# Mega_2560_Z21.net
KiCad netlist of a schematic drawn in EAGLE
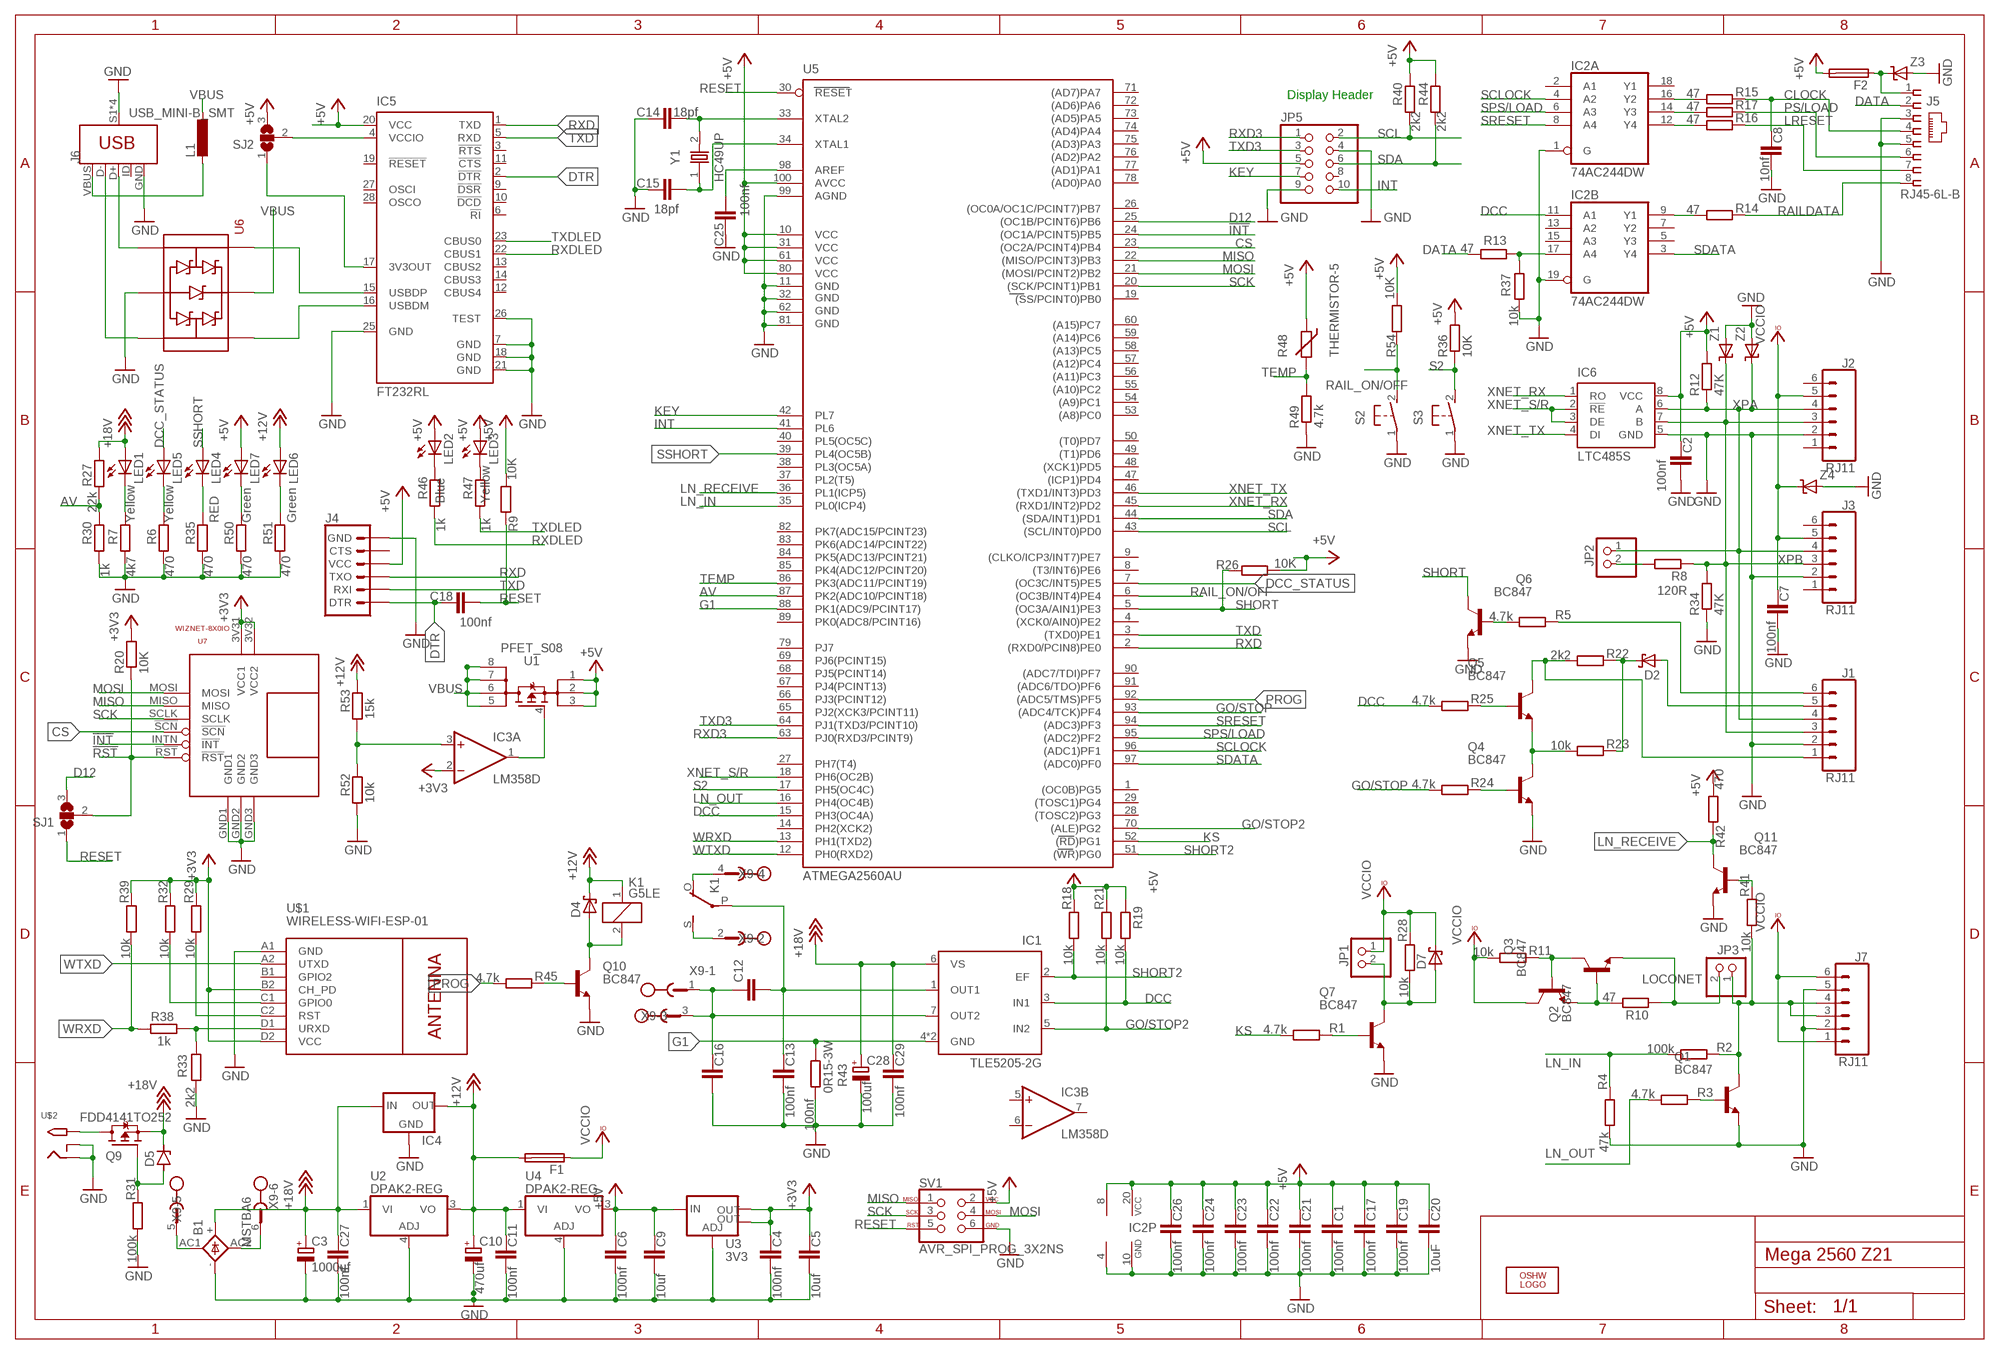
[diagram p0: schematic, sheet 1]

(export (version "E")
  (design (tool "Eeschema 10.0.6"))
  (components
    (comp (ref "B1")
      (value "BRIDGE_RECTIFIER_6AMP")
      (footprint "eagle-import:KBU-6D")
      (fields (field (name "PARTNUMBER") "KBU 6D"))
      (libsource (lib "eagle-import") (part "BRIDGE_RECTIFIER_6AMP"))
    )
    (comp (ref "C1")
      (value "100nf")
      (footprint "eagle-import:C0603")
      (libsource (lib "eagle-import") (part "C-EUC0603"))
    )
    (comp (ref "C2")
      (value "100nf")
      (footprint "eagle-import:C0603")
      (libsource (lib "eagle-import") (part "C-EUC0603"))
    )
    (comp (ref "C3")
      (value "1000uf")
      (footprint "eagle-import:E5-13")
      (libsource (lib "eagle-import") (part "rcl_334_CPOL-EUE5-13"))
    )
    (comp (ref "C4")
      (value "100nf")
      (footprint "eagle-import:C0603")
      (libsource (lib "eagle-import") (part "C-EUC0603"))
    )
    (comp (ref "C5")
      (value "10uf")
      (footprint "eagle-import:C0805")
      (libsource (lib "eagle-import") (part "C-EUC0805"))
    )
    (comp (ref "C6")
      (value "100nf")
      (footprint "eagle-import:C0603")
      (libsource (lib "eagle-import") (part "C-EUC0603"))
    )
    (comp (ref "C7")
      (value "100nf")
      (footprint "eagle-import:C0603")
      (libsource (lib "eagle-import") (part "C-EUC0603"))
    )
    (comp (ref "C8")
      (value "10nf")
      (footprint "eagle-import:C0603")
      (libsource (lib "eagle-import") (part "C-EUC0603"))
    )
    (comp (ref "C9")
      (value "10uf")
      (footprint "eagle-import:C0805")
      (libsource (lib "eagle-import") (part "C-EUC0805"))
    )
    (comp (ref "C10")
      (value "470uf")
      (footprint "eagle-import:E5-13")
      (libsource (lib "eagle-import") (part "rcl_334_CPOL-EUE5-13"))
    )
    (comp (ref "C11")
      (value "100nf")
      (footprint "eagle-import:C0603")
      (libsource (lib "eagle-import") (part "C-EUC0603"))
    )
    (comp (ref "C12")
      (value "C-EUC1812")
      (footprint "eagle-import:C1812")
      (libsource (lib "eagle-import") (part "C-EUC1812"))
    )
    (comp (ref "C13")
      (value "100nf")
      (footprint "eagle-import:C1206")
      (libsource (lib "eagle-import") (part "C-EUC1206"))
    )
    (comp (ref "C14")
      (value "18pf")
      (footprint "eagle-import:C0603")
      (libsource (lib "eagle-import") (part "C-EUC0603"))
    )
    (comp (ref "C15")
      (value "18pf")
      (footprint "eagle-import:C0603")
      (libsource (lib "eagle-import") (part "C-EUC0603"))
    )
    (comp (ref "C16")
      (value "100nf")
      (footprint "eagle-import:C1206")
      (libsource (lib "eagle-import") (part "C-EUC1206"))
    )
    (comp (ref "C17")
      (value "100nf")
      (footprint "eagle-import:C0603")
      (libsource (lib "eagle-import") (part "C-EUC0603"))
    )
    (comp (ref "C18")
      (value "100nf")
      (footprint "eagle-import:C0603")
      (libsource (lib "eagle-import") (part "C-EUC0603"))
    )
    (comp (ref "C19")
      (value "100nf")
      (footprint "eagle-import:C0603")
      (libsource (lib "eagle-import") (part "C-EUC0603"))
    )
    (comp (ref "C20")
      (value "10uF")
      (footprint "eagle-import:C0805")
      (libsource (lib "eagle-import") (part "C-EUC0805"))
    )
    (comp (ref "C21")
      (value "100nf")
      (footprint "eagle-import:C0603")
      (libsource (lib "eagle-import") (part "C-EUC0603"))
    )
    (comp (ref "C22")
      (value "100nf")
      (footprint "eagle-import:C0603")
      (libsource (lib "eagle-import") (part "C-EUC0603"))
    )
    (comp (ref "C23")
      (value "100nf")
      (footprint "eagle-import:C0603")
      (libsource (lib "eagle-import") (part "C-EUC0603"))
    )
    (comp (ref "C24")
      (value "100nf")
      (footprint "eagle-import:C0603")
      (libsource (lib "eagle-import") (part "C-EUC0603"))
    )
    (comp (ref "C25")
      (value "100nf")
      (footprint "eagle-import:C0603")
      (libsource (lib "eagle-import") (part "C-EUC0603"))
    )
    (comp (ref "C26")
      (value "100nf")
      (footprint "eagle-import:C0603")
      (libsource (lib "eagle-import") (part "C-EUC0603"))
    )
    (comp (ref "C27")
      (value "100nf")
      (footprint "eagle-import:C0805")
      (libsource (lib "eagle-import") (part "C-EUC0805"))
    )
    (comp (ref "C28")
      (value "100uf")
      (footprint "eagle-import:E2-5")
      (libsource (lib "eagle-import") (part "CPOL-EUE2-5"))
    )
    (comp (ref "C29")
      (value "100nf")
      (footprint "eagle-import:C1206")
      (libsource (lib "eagle-import") (part "C-EUC1206"))
    )
    (comp (ref "D2")
      (value "MICROSMD-SCHOTTKY-DIODE")
      (footprint "eagle-import:MICROSMP")
      (fields (field (name "MANUFACTURER") "Vishay"))
      (libsource (lib "eagle-import") (part "MICROSMD-SCHOTTKY-DIODE"))
    )
    (comp (ref "D4")
      (value "MICROSMD-SCHOTTKY-DIODE")
      (footprint "eagle-import:MICROSMP")
      (fields (field (name "MANUFACTURER") "Vishay"))
      (libsource (lib "eagle-import") (part "MICROSMD-SCHOTTKY-DIODE"))
    )
    (comp (ref "D5")
      (value "ZENER-DIODESOT23")
      (footprint "eagle-import:SOT23")
      (libsource (lib "eagle-import") (part "ZENER-DIODESOT23"))
    )
    (comp (ref "D7")
      (value "MICROSMD-SCHOTTKY-DIODE")
      (footprint "eagle-import:MICROSMP")
      (fields (field (name "MANUFACTURER") "Vishay"))
      (libsource (lib "eagle-import") (part "MICROSMD-SCHOTTKY-DIODE"))
    )
    (comp (ref "F1")
      (value "TE5")
      (footprint "eagle-import:TE5")
      (libsource (lib "eagle-import") (part "TE5"))
    )
    (comp (ref "F2")
      (value "TE5")
      (footprint "eagle-import:TE5")
      (libsource (lib "eagle-import") (part "TE5"))
    )
    (comp (ref "IC1")
      (value "TLE5205-2G")
      (footprint "eagle-import:P-TO263-7-1")
      (libsource (lib "eagle-import") (part "TLE5205-2G"))
    )
    (comp (ref "IC2")
      (value "74AC244DW")
      (footprint "eagle-import:SO20W")
      (libsource (lib "eagle-import") (part "74244DWAC"))
    )
    (comp (ref "IC3")
      (value "LM358D")
      (footprint "eagle-import:SO08")
      (libsource (lib "eagle-import") (part "LM358D"))
    )
    (comp (ref "IC4")
      (value "78XXS")
      (footprint "eagle-import:78XXS")
      (libsource (lib "eagle-import") (part "78XXS"))
    )
    (comp (ref "IC5")
      (value "FT232RL")
      (footprint "eagle-import:SSOP28")
      (libsource (lib "eagle-import") (part "FT232RL"))
    )
    (comp (ref "IC6")
      (value "LTC485S")
      (footprint "eagle-import:SOIC8")
      (libsource (lib "eagle-import") (part "LTC485S"))
    )
    (comp (ref "J1")
      (value "RJ11")
      (footprint "eagle-import:RJ11-6")
      (libsource (lib "eagle-import") (part "RJ11-6"))
    )
    (comp (ref "J2")
      (value "RJ11")
      (footprint "eagle-import:RJ11-6")
      (libsource (lib "eagle-import") (part "RJ11-6"))
    )
    (comp (ref "J3")
      (value "RJ11")
      (footprint "eagle-import:RJ11-6")
      (libsource (lib "eagle-import") (part "RJ11-6"))
    )
    (comp (ref "J4")
      (value "6_PIN_SERIAL_TARGET")
      (footprint "eagle-import:1X06")
      (libsource (lib "eagle-import") (part "6_PIN_SERIAL_TARGET"))
    )
    (comp (ref "J5")
      (value "RJ45-6L-B")
      (footprint "eagle-import:RJ45-NO-SHIELD")
      (libsource (lib "eagle-import") (part "RJ45-6L-B"))
    )
    (comp (ref "J6")
      (value "USB_MINI-B_SMT")
      (footprint "eagle-import:USB-MINIB")
      (libsource (lib "eagle-import") (part "USB_MINI-B_SMT"))
    )
    (comp (ref "J7")
      (value "RJ11")
      (footprint "eagle-import:RJ11-6")
      (libsource (lib "eagle-import") (part "RJ11-6"))
    )
    (comp (ref "JP1")
      (value "PINHD-1X2")
      (footprint "eagle-import:1X02")
      (libsource (lib "eagle-import") (part "PINHD-1X2"))
    )
    (comp (ref "JP2")
      (value "PINHD-1X2")
      (footprint "eagle-import:1X02")
      (libsource (lib "eagle-import") (part "PINHD-1X2"))
    )
    (comp (ref "JP3")
      (value "PINHD-1X2")
      (footprint "eagle-import:1X02")
      (libsource (lib "eagle-import") (part "PINHD-1X2"))
    )
    (comp (ref "JP5")
      (value "PINHD-2X5")
      (footprint "eagle-import:2X05")
      (libsource (lib "eagle-import") (part "PINHD-2X5"))
    )
    (comp (ref "K1")
      (value "G5LE")
      (footprint "eagle-import:G5LE")
      (libsource (lib "eagle-import") (part "G5LE"))
    )
    (comp (ref "L1")
      (value "L-EUL2012C")
      (footprint "eagle-import:L2012C")
      (libsource (lib "eagle-import") (part "L-EUL2012C"))
    )
    (comp (ref "LED1")
      (value "Yellow")
      (footprint "eagle-import:LED3MM")
      (libsource (lib "eagle-import") (part "LED3MM"))
    )
    (comp (ref "LED2")
      (value "Blue")
      (footprint "eagle-import:LED3MM")
      (libsource (lib "eagle-import") (part "LED3MM"))
    )
    (comp (ref "LED3")
      (value "Yellow")
      (footprint "eagle-import:LED3MM")
      (libsource (lib "eagle-import") (part "LED3MM"))
    )
    (comp (ref "LED4")
      (value "RED")
      (footprint "eagle-import:LED3MM")
      (libsource (lib "eagle-import") (part "LED3MM"))
    )
    (comp (ref "LED5")
      (value "Yellow")
      (footprint "eagle-import:LED3MM")
      (libsource (lib "eagle-import") (part "LED3MM"))
    )
    (comp (ref "LED6")
      (value "Green")
      (footprint "eagle-import:LED3MM")
      (libsource (lib "eagle-import") (part "LED3MM"))
    )
    (comp (ref "LED7")
      (value "Green")
      (footprint "eagle-import:LED3MM")
      (libsource (lib "eagle-import") (part "LED3MM"))
    )
    (comp (ref "LOGO1")
      (value "OSHW_LOGO_6MILX0200-NT")
      (footprint "eagle-import:OSHW_6X200_NOTEXT")
      (libsource (lib "eagle-import") (part "OSHW_LOGO_6MILX0200-NT"))
    )
    (comp (ref "Q1")
      (value "BC847")
      (footprint "eagle-import:SOT23")
      (libsource (lib "eagle-import") (part "BC847"))
    )
    (comp (ref "Q2")
      (value "BC847")
      (footprint "eagle-import:SOT23")
      (libsource (lib "eagle-import") (part "BC847"))
    )
    (comp (ref "Q3")
      (value "BC847")
      (footprint "eagle-import:SOT23")
      (libsource (lib "eagle-import") (part "BC847"))
    )
    (comp (ref "Q4")
      (value "BC847")
      (footprint "eagle-import:SOT23")
      (libsource (lib "eagle-import") (part "BC847"))
    )
    (comp (ref "Q5")
      (value "BC847")
      (footprint "eagle-import:SOT23")
      (libsource (lib "eagle-import") (part "BC847"))
    )
    (comp (ref "Q6")
      (value "BC847")
      (footprint "eagle-import:SOT23")
      (libsource (lib "eagle-import") (part "BC847"))
    )
    (comp (ref "Q7")
      (value "BC847")
      (footprint "eagle-import:SOT23")
      (libsource (lib "eagle-import") (part "BC847"))
    )
    (comp (ref "Q9")
      (value "FDD4141TO252")
      (footprint "eagle-import:TO252")
      (libsource (lib "eagle-import") (part "FDD4141TO252"))
    )
    (comp (ref "Q10")
      (value "BC847")
      (footprint "eagle-import:SOT23")
      (libsource (lib "eagle-import") (part "BC847"))
    )
    (comp (ref "Q11")
      (value "BC847")
      (footprint "eagle-import:SOT23")
      (libsource (lib "eagle-import") (part "BC847"))
    )
    (comp (ref "R1")
      (value "4.7k")
      (footprint "eagle-import:R0603")
      (libsource (lib "eagle-import") (part "R-EU_R0603"))
    )
    (comp (ref "R2")
      (value "100k")
      (footprint "eagle-import:R0603")
      (libsource (lib "eagle-import") (part "R-EU_R0603"))
    )
    (comp (ref "R3")
      (value "4.7k")
      (footprint "eagle-import:R0603")
      (libsource (lib "eagle-import") (part "R-EU_R0603"))
    )
    (comp (ref "R4")
      (value "47k")
      (footprint "eagle-import:R0603")
      (libsource (lib "eagle-import") (part "R-EU_R0603"))
    )
    (comp (ref "R5")
      (value "4.7k")
      (footprint "eagle-import:R0603")
      (libsource (lib "eagle-import") (part "R-EU_R0603"))
    )
    (comp (ref "R6")
      (value "470")
      (footprint "eagle-import:R0603")
      (libsource (lib "eagle-import") (part "R-EU_R0603"))
    )
    (comp (ref "R7")
      (value "4k7")
      (footprint "eagle-import:R0603")
      (libsource (lib "eagle-import") (part "R-EU_R0603"))
    )
    (comp (ref "R8")
      (value "120R")
      (footprint "eagle-import:R0603")
      (libsource (lib "eagle-import") (part "R-EU_R0603"))
    )
    (comp (ref "R9")
      (value "10K")
      (footprint "eagle-import:R0603")
      (libsource (lib "eagle-import") (part "R-EU_R0603"))
    )
    (comp (ref "R10")
      (value "47")
      (footprint "eagle-import:R0603")
      (libsource (lib "eagle-import") (part "R-EU_R0603"))
    )
    (comp (ref "R11")
      (value "10k")
      (footprint "eagle-import:R0603")
      (libsource (lib "eagle-import") (part "R-EU_R0603"))
    )
    (comp (ref "R12")
      (value "47K")
      (footprint "eagle-import:R0603")
      (libsource (lib "eagle-import") (part "R-EU_R0603"))
    )
    (comp (ref "R13")
      (value "47")
      (footprint "eagle-import:R0603")
      (libsource (lib "eagle-import") (part "R-EU_R0603"))
    )
    (comp (ref "R14")
      (value "47")
      (footprint "eagle-import:R0603")
      (libsource (lib "eagle-import") (part "R-EU_R0603"))
    )
    (comp (ref "R15")
      (value "47")
      (footprint "eagle-import:R0603")
      (libsource (lib "eagle-import") (part "R-EU_R0603"))
    )
    (comp (ref "R16")
      (value "47")
      (footprint "eagle-import:R0603")
      (libsource (lib "eagle-import") (part "R-EU_R0603"))
    )
    (comp (ref "R17")
      (value "47")
      (footprint "eagle-import:R0603")
      (libsource (lib "eagle-import") (part "R-EU_R0603"))
    )
    (comp (ref "R18")
      (value "10k")
      (footprint "eagle-import:R0603")
      (libsource (lib "eagle-import") (part "R-EU_R0603"))
    )
    (comp (ref "R19")
      (value "10k")
      (footprint "eagle-import:R0603")
      (libsource (lib "eagle-import") (part "R-EU_R0603"))
    )
    (comp (ref "R20")
      (value "10K")
      (footprint "eagle-import:R0603")
      (libsource (lib "eagle-import") (part "R-EU_R0603"))
    )
    (comp (ref "R21")
      (value "10k")
      (footprint "eagle-import:R0603")
      (libsource (lib "eagle-import") (part "R-EU_R0603"))
    )
    (comp (ref "R22")
      (value "2k2")
      (footprint "eagle-import:R0603")
      (libsource (lib "eagle-import") (part "R-EU_R0603"))
    )
    (comp (ref "R23")
      (value "10k")
      (footprint "eagle-import:R0603")
      (libsource (lib "eagle-import") (part "R-EU_R0603"))
    )
    (comp (ref "R24")
      (value "4.7k")
      (footprint "eagle-import:R0603")
      (libsource (lib "eagle-import") (part "R-EU_R0603"))
    )
    (comp (ref "R25")
      (value "4.7k")
      (footprint "eagle-import:R0603")
      (libsource (lib "eagle-import") (part "R-EU_R0603"))
    )
    (comp (ref "R26")
      (value "10K")
      (footprint "eagle-import:R0603")
      (libsource (lib "eagle-import") (part "R-EU_R0603"))
    )
    (comp (ref "R27")
      (value "22k")
      (footprint "eagle-import:R0603")
      (libsource (lib "eagle-import") (part "R-EU_R0603"))
    )
    (comp (ref "R28")
      (value "10k")
      (footprint "eagle-import:R0603")
      (libsource (lib "eagle-import") (part "R-EU_R0603"))
    )
    (comp (ref "R29")
      (value "10k")
      (footprint "eagle-import:R0603")
      (libsource (lib "eagle-import") (part "R-EU_R0603"))
    )
    (comp (ref "R30")
      (value "1k")
      (footprint "eagle-import:R0603")
      (libsource (lib "eagle-import") (part "R-EU_R0603"))
    )
    (comp (ref "R31")
      (value "100k")
      (footprint "eagle-import:R0603")
      (libsource (lib "eagle-import") (part "R-EU_R0603"))
    )
    (comp (ref "R32")
      (value "10k")
      (footprint "eagle-import:R0603")
      (libsource (lib "eagle-import") (part "R-EU_R0603"))
    )
    (comp (ref "R33")
      (value "2k2")
      (footprint "eagle-import:R0603")
      (libsource (lib "eagle-import") (part "R-EU_R0603"))
    )
    (comp (ref "R34")
      (value "47K")
      (footprint "eagle-import:R0603")
      (libsource (lib "eagle-import") (part "R-EU_R0603"))
    )
    (comp (ref "R35")
      (value "470")
      (footprint "eagle-import:R0603")
      (libsource (lib "eagle-import") (part "R-EU_R0603"))
    )
    (comp (ref "R36")
      (value "10K")
      (footprint "eagle-import:R0603")
      (libsource (lib "eagle-import") (part "R-EU_R0603"))
    )
    (comp (ref "R37")
      (value "10k")
      (footprint "eagle-import:R0603")
      (libsource (lib "eagle-import") (part "R-EU_R0603"))
    )
    (comp (ref "R38")
      (value "1k")
      (footprint "eagle-import:R0603")
      (libsource (lib "eagle-import") (part "R-EU_R0603"))
    )
    (comp (ref "R39")
      (value "10k")
      (footprint "eagle-import:R0603")
      (libsource (lib "eagle-import") (part "R-EU_R0603"))
    )
    (comp (ref "R40")
      (value "2k2")
      (footprint "eagle-import:R0603")
      (libsource (lib "eagle-import") (part "R-EU_R0603"))
    )
    (comp (ref "R41")
      (value "10k")
      (footprint "eagle-import:R0603")
      (libsource (lib "eagle-import") (part "R-EU_R0603"))
    )
    (comp (ref "R42")
      (value "470")
      (footprint "eagle-import:R0603")
      (libsource (lib "eagle-import") (part "R-EU_R0603"))
    )
    (comp (ref "R43")
      (value "0R15-3W")
      (footprint "eagle-import:P0817V")
      (libsource (lib "eagle-import") (part "rcl_334_R-EU_0817/7V"))
    )
    (comp (ref "R44")
      (value "2k2")
      (footprint "eagle-import:R0603")
      (libsource (lib "eagle-import") (part "R-EU_R0603"))
    )
    (comp (ref "R45")
      (value "4.7k")
      (footprint "eagle-import:R0603")
      (libsource (lib "eagle-import") (part "R-EU_R0603"))
    )
    (comp (ref "R46")
      (value "1k")
      (footprint "eagle-import:R0603")
      (libsource (lib "eagle-import") (part "R-EU_R0603"))
    )
    (comp (ref "R47")
      (value "1k")
      (footprint "eagle-import:R0603")
      (libsource (lib "eagle-import") (part "R-EU_R0603"))
    )
    (comp (ref "R48")
      (value "THERMISTOR-5")
      (footprint "eagle-import:R-5")
      (libsource (lib "eagle-import") (part "THERMISTOR-5"))
    )
    (comp (ref "R49")
      (value "4.7k")
      (footprint "eagle-import:R0603")
      (libsource (lib "eagle-import") (part "R-EU_R0603"))
    )
    (comp (ref "R50")
      (value "470")
      (footprint "eagle-import:R0603")
      (libsource (lib "eagle-import") (part "R-EU_R0603"))
    )
    (comp (ref "R51")
      (value "470")
      (footprint "eagle-import:R0603")
      (libsource (lib "eagle-import") (part "R-EU_R0603"))
    )
    (comp (ref "R52")
      (value "10k")
      (footprint "eagle-import:R0603")
      (libsource (lib "eagle-import") (part "R-EU_R0603"))
    )
    (comp (ref "R53")
      (value "15k")
      (footprint "eagle-import:R0603")
      (libsource (lib "eagle-import") (part "R-EU_R0603"))
    )
    (comp (ref "R54")
      (value "10K")
      (footprint "eagle-import:R0603")
      (libsource (lib "eagle-import") (part "R-EU_R0603"))
    )
    (comp (ref "S2")
      (value "31-XX")
      (footprint "eagle-import:B3F-31XX")
      (fields (field (name "MPN") "B3F-3100"))
      (libsource (lib "eagle-import") (part "31-XX"))
    )
    (comp (ref "S3")
      (value "31-XX")
      (footprint "eagle-import:B3F-31XX")
      (fields (field (name "MPN") "B3F-3100"))
      (libsource (lib "eagle-import") (part "31-XX"))
    )
    (comp (ref "SJ1")
      (value "SJ2W")
      (footprint "eagle-import:SJ_2")
      (libsource (lib "eagle-import") (part "SJ2W"))
    )
    (comp (ref "SJ2")
      (value "SJ2W")
      (footprint "eagle-import:SJ_2")
      (libsource (lib "eagle-import") (part "SJ2W"))
    )
    (comp (ref "SV1")
      (value "AVR_SPI_PROG_3X2NS")
      (footprint "eagle-import:2X3-NS")
      (libsource (lib "eagle-import") (part "AVR_SPI_PROG_3X2NS"))
    )
    (comp (ref "U$1")
      (value "WIRELESS-WIFI-ESP-01")
      (footprint "eagle-import:WIRELESS-WIFI-ESP-01")
      (libsource (lib "eagle-import") (part "WIRELESS-WIFI-ESP-01"))
    )
    (comp (ref "U$2")
      (value "2.1MMJACKTHM")
      (footprint "eagle-import:PJ-102A")
      (libsource (lib "eagle-import") (part "2.1MMJACKTHM"))
    )
    (comp (ref "U1")
      (value "PFET_S08")
      (footprint "eagle-import:SO08")
      (fields (field (name "MANUFACTURER") "Infineon") (field (name "PARTNUMBER") "IRF9388TRFPBF"))
      (libsource (lib "eagle-import") (part "PFET_S08"))
    )
    (comp (ref "U2")
      (value "DPAK2-REG")
      (footprint "eagle-import:DPAK2")
      (fields (field (name "PARTNUMBER") "MC78M05CDTG"))
      (libsource (lib "eagle-import") (part "DPAK2-REG"))
    )
    (comp (ref "U3")
      (value "3V3")
      (footprint "eagle-import:SOT223")
      (libsource (lib "eagle-import") (part "V_REG_LM1117SOT223"))
    )
    (comp (ref "U4")
      (value "DPAK2-REG")
      (footprint "eagle-import:DPAK2")
      (fields (field (name "PARTNUMBER") "MC78M05CDTG"))
      (libsource (lib "eagle-import") (part "DPAK2-REG"))
    )
    (comp (ref "U5")
      (value "ATMEGA2560AU")
      (footprint "eagle-import:TQFP100")
      (libsource (lib "eagle-import") (part "ATMEGA2560AU"))
    )
    (comp (ref "U6")
      (value "UABLC6-2SOT23-6L")
      (footprint "eagle-import:SOT95P280X145-6N")
      (libsource (lib "eagle-import") (part "UABLC6-2SOT23-6L"))
    )
    (comp (ref "U7")
      (value "WIZNET-8X0IO")
      (footprint "eagle-import:WIZ850IO")
      (fields (field (name "MANUFACTURER") "Wiznet") (field (name "PARTNUMBER") "W850io"))
      (libsource (lib "eagle-import") (part "WIZNET-8X0IO"))
    )
    (comp (ref "X9")
      (value "MSTBA6")
      (footprint "eagle-import:MSTBA6")
      (fields (field (name "MF") "FARNELL") (field (name "MPN") "1757284"))
      (libsource (lib "eagle-import") (part "MSTBA6"))
    )
    (comp (ref "Y1")
      (value "HC49UP")
      (footprint "eagle-import:HC49UP")
      (libsource (lib "eagle-import") (part "HC49UP"))
    )
    (comp (ref "Z1")
      (value "TRANSZORB-SMA")
      (footprint "eagle-import:SMA")
      (libsource (lib "eagle-import") (part "TRANSZORB-SMA"))
    )
    (comp (ref "Z2")
      (value "TRANSZORB-SMA")
      (footprint "eagle-import:SMA")
      (libsource (lib "eagle-import") (part "TRANSZORB-SMA"))
    )
    (comp (ref "Z3")
      (value "TRANSZORB-SMA")
      (footprint "eagle-import:SMA")
      (libsource (lib "eagle-import") (part "TRANSZORB-SMA"))
    )
    (comp (ref "Z4")
      (value "TRANSZORB-SMA")
      (footprint "eagle-import:SMA")
      (libsource (lib "eagle-import") (part "TRANSZORB-SMA"))
    )
  )
  (nets
    (net (code "1") (name "+3V3") (class "Default")
      (node (ref "C4") (pin "1") (pinfunction "1_1") (pintype "passive"))
      (node (ref "C5") (pin "1") (pinfunction "1_1") (pintype "passive"))
      (node (ref "IC3") (pin "2") (pinfunction "-IN_2") (pintype "input"))
      (node (ref "R20") (pin "2") (pinfunction "2_2") (pintype "passive"))
      (node (ref "R29") (pin "1") (pinfunction "1_1") (pintype "passive"))
      (node (ref "R32") (pin "1") (pinfunction "1_1") (pintype "passive"))
      (node (ref "R39") (pin "1") (pinfunction "1_1") (pintype "passive"))
      (node (ref "U$1") (pin "B2") (pinfunction "CH_PD_B2") (pintype "bidirectional"))
      (node (ref "U$1") (pin "D2") (pinfunction "VCC_D2") (pintype "power_in"))
      (node (ref "U3") (pin "2") (pinfunction "OUT_2") (pintype "output"))
      (node (ref "U3") (pin "4") (pinfunction "OUT_4") (pintype "output"))
      (node (ref "U7") (pin "3V31") (pinfunction "VCC1_3V31") (pintype "power_in"))
      (node (ref "U7") (pin "3V32") (pinfunction "VCC2_3V32") (pintype "power_in"))
    )
    (net (code "2") (name "+5V") (class "Default")
      (node (ref "C1") (pin "1") (pinfunction "1_1") (pintype "passive"))
      (node (ref "C17") (pin "1") (pinfunction "1_1") (pintype "passive"))
      (node (ref "C19") (pin "1") (pinfunction "1_1") (pintype "passive"))
      (node (ref "C2") (pin "1") (pinfunction "1_1") (pintype "passive"))
      (node (ref "C20") (pin "1") (pinfunction "1_1") (pintype "passive"))
      (node (ref "C21") (pin "1") (pinfunction "1_1") (pintype "passive"))
      (node (ref "C22") (pin "1") (pinfunction "1_1") (pintype "passive"))
      (node (ref "C23") (pin "1") (pinfunction "1_1") (pintype "passive"))
      (node (ref "C24") (pin "1") (pinfunction "1_1") (pintype "passive"))
      (node (ref "C26") (pin "1") (pinfunction "1_1") (pintype "passive"))
      (node (ref "C6") (pin "1") (pinfunction "1_1") (pintype "passive"))
      (node (ref "C9") (pin "1") (pinfunction "1_1") (pintype "passive"))
      (node (ref "F2") (pin "2") (pinfunction "2_2") (pintype "passive"))
      (node (ref "IC2") (pin "20") (pinfunction "VCC_20") (pintype "power_in"))
      (node (ref "IC3") (pin "8") (pinfunction "V+_8") (pintype "power_in"))
      (node (ref "IC5") (pin "20") (pinfunction "VCC_20") (pintype "power_in"))
      (node (ref "IC6") (pin "8") (pinfunction "VCC_8") (pintype "input"))
      (node (ref "J4") (pin "4") (pinfunction "VCC_4") (pintype "passive"))
      (node (ref "JP5") (pin "5") (pinfunction "5_5") (pintype "passive"))
      (node (ref "LED2") (pin "A") (pinfunction "A_A") (pintype "passive"))
      (node (ref "LED3") (pin "A") (pinfunction "A_A") (pintype "passive"))
      (node (ref "LED7") (pin "A") (pinfunction "A_A") (pintype "passive"))
      (node (ref "R12") (pin "2") (pinfunction "2_2") (pintype "passive"))
      (node (ref "R18") (pin "1") (pinfunction "1_1") (pintype "passive"))
      (node (ref "R19") (pin "1") (pinfunction "1_1") (pintype "passive"))
      (node (ref "R21") (pin "1") (pinfunction "1_1") (pintype "passive"))
      (node (ref "R26") (pin "2") (pinfunction "2_2") (pintype "passive"))
      (node (ref "R36") (pin "2") (pinfunction "2_2") (pintype "passive"))
      (node (ref "R40") (pin "2") (pinfunction "2_2") (pintype "passive"))
      (node (ref "R42") (pin "2") (pinfunction "2_2") (pintype "passive"))
      (node (ref "R44") (pin "2") (pinfunction "2_2") (pintype "passive"))
      (node (ref "R48") (pin "1") (pinfunction "1_1") (pintype "passive"))
      (node (ref "R54") (pin "2") (pinfunction "2_2") (pintype "passive"))
      (node (ref "R9") (pin "2") (pinfunction "2_2") (pintype "passive"))
      (node (ref "SJ2") (pin "3") (pinfunction "3_3") (pintype "passive"))
      (node (ref "SV1") (pin "2") (pinfunction "2_2") (pintype "passive"))
      (node (ref "U1") (pin "1") (pinfunction "S1_1") (pintype "passive"))
      (node (ref "U1") (pin "2") (pinfunction "S2_2") (pintype "passive"))
      (node (ref "U1") (pin "3") (pinfunction "S3_3") (pintype "passive"))
      (node (ref "U3") (pin "3") (pinfunction "IN_3") (pintype "input"))
      (node (ref "U4") (pin "3") (pinfunction "VO_3") (pintype "passive"))
      (node (ref "U5") (pin "10") (pinfunction "VCC_10") (pintype "power_in"))
      (node (ref "U5") (pin "100") (pinfunction "AVCC_100") (pintype "power_in"))
      (node (ref "U5") (pin "31") (pinfunction "VCC1_31") (pintype "power_in"))
      (node (ref "U5") (pin "61") (pinfunction "VCC2_61") (pintype "power_in"))
      (node (ref "U5") (pin "80") (pinfunction "VCC3_80") (pintype "power_in"))
    )
    (net (code "3") (name "+12V") (class "Default")
      (node (ref "C10") (pin "+") (pinfunction "+_+") (pintype "passive"))
      (node (ref "C11") (pin "1") (pinfunction "1_1") (pintype "passive"))
      (node (ref "D4") (pin "C") (pinfunction "C_C") (pintype "passive"))
      (node (ref "F1") (pin "2") (pinfunction "2_2") (pintype "passive"))
      (node (ref "IC4") (pin "OUT") (pinfunction "OUT_OUT") (pintype "passive"))
      (node (ref "K1") (pin "1") (pinfunction "1_1") (pintype "passive"))
      (node (ref "LED6") (pin "A") (pinfunction "A_A") (pintype "passive"))
      (node (ref "R53") (pin "2") (pinfunction "2_2") (pintype "passive"))
      (node (ref "U2") (pin "3") (pinfunction "VO_3") (pintype "passive"))
      (node (ref "U4") (pin "1") (pinfunction "VI_1") (pintype "input"))
    )
    (net (code "4") (name "+18V") (class "Default")
      (node (ref "B1") (pin "+") (pinfunction "+_+") (pintype "passive"))
      (node (ref "C27") (pin "1") (pinfunction "1_1") (pintype "passive"))
      (node (ref "C28") (pin "+") (pinfunction "+_+") (pintype "passive"))
      (node (ref "C29") (pin "1") (pinfunction "1_1") (pintype "passive"))
      (node (ref "C3") (pin "+") (pinfunction "+_+") (pintype "passive"))
      (node (ref "D5") (pin "3") (pinfunction "C_3") (pintype "passive"))
      (node (ref "IC1") (pin "6") (pinfunction "VS_6") (pintype "input"))
      (node (ref "IC4") (pin "IN") (pinfunction "IN_IN") (pintype "input"))
      (node (ref "LED1") (pin "A") (pinfunction "A_A") (pintype "passive"))
      (node (ref "Q9") (pin "2") (pinfunction "S_2") (pintype "passive"))
      (node (ref "R27") (pin "2") (pinfunction "2_2") (pintype "passive"))
      (node (ref "U2") (pin "1") (pinfunction "VI_1") (pintype "input"))
    )
    (net (code "5") (name "/AV") (class "Default")
      (node (ref "R27") (pin "1") (pinfunction "1_1") (pintype "passive"))
      (node (ref "R30") (pin "2") (pinfunction "2_2") (pintype "passive"))
      (node (ref "U5") (pin "87") (pinfunction "PK2(ADC10/PCINT18)_87") (pintype "bidirectional"))
    )
    (net (code "6") (name "/CLOCK") (class "Default")
      (node (ref "C8") (pin "1") (pinfunction "1_1") (pintype "passive"))
      (node (ref "J5") (pin "4") (pinfunction "4_4") (pintype "passive"))
      (node (ref "R15") (pin "1") (pinfunction "1_1") (pintype "passive"))
    )
    (net (code "7") (name "/D12") (class "Default")
      (node (ref "SJ1") (pin "3") (pinfunction "3_3") (pintype "passive"))
      (node (ref "U5") (pin "25") (pinfunction "(OC1B/PCINT6)PB6_25") (pintype "bidirectional"))
    )
    (net (code "8") (name "/DATA") (class "Default")
      (node (ref "J5") (pin "2") (pinfunction "2_2") (pintype "passive"))
      (node (ref "R13") (pin "2") (pinfunction "2_2") (pintype "passive"))
    )
    (net (code "9") (name "/DCC") (class "Default")
      (node (ref "IC1") (pin "3") (pinfunction "IN1_3") (pintype "input"))
      (node (ref "IC2") (pin "11") (pinfunction "A1_11") (pintype "input"))
      (node (ref "R19") (pin "2") (pinfunction "2_2") (pintype "passive"))
      (node (ref "R25") (pin "2") (pinfunction "2_2") (pintype "passive"))
      (node (ref "U5") (pin "15") (pinfunction "PH3(OC4A)_15") (pintype "bidirectional"))
    )
    (net (code "10") (name "/GO{slash}STOP") (class "Default")
      (node (ref "R24") (pin "2") (pinfunction "2_2") (pintype "passive"))
      (node (ref "U5") (pin "93") (pinfunction "(ADC4/TCK)PF4_93") (pintype "bidirectional"))
    )
    (net (code "11") (name "/GO{slash}STOP2") (class "Default")
      (node (ref "IC1") (pin "5") (pinfunction "IN2_5") (pintype "input"))
      (node (ref "R21") (pin "2") (pinfunction "2_2") (pintype "passive"))
      (node (ref "U5") (pin "70") (pinfunction "(ALE)PG2_70") (pintype "bidirectional"))
    )
    (net (code "12") (name "/INT") (class "Default")
      (node (ref "JP5") (pin "10") (pinfunction "10_10") (pintype "passive"))
      (node (ref "U5") (pin "41") (pinfunction "PL6_41") (pintype "bidirectional"))
    )
    (net (code "13") (name "/KEY") (class "Default")
      (node (ref "JP5") (pin "7") (pinfunction "7_7") (pintype "passive"))
      (node (ref "U5") (pin "42") (pinfunction "PL7_42") (pintype "bidirectional"))
    )
    (net (code "14") (name "/KS") (class "Default")
      (node (ref "R1") (pin "2") (pinfunction "2_2") (pintype "passive"))
      (node (ref "U5") (pin "52") (pinfunction "(RD)PG1_52") (pintype "bidirectional"))
    )
    (net (code "15") (name "/LN_IN") (class "Default")
      (node (ref "R2") (pin "2") (pinfunction "2_2") (pintype "passive"))
      (node (ref "R4") (pin "1") (pinfunction "1_1") (pintype "passive"))
      (node (ref "U5") (pin "35") (pinfunction "PL0(ICP4)_35") (pintype "bidirectional"))
    )
    (net (code "16") (name "/LN_OUT") (class "Default")
      (node (ref "R3") (pin "2") (pinfunction "2_2") (pintype "passive"))
      (node (ref "U5") (pin "16") (pinfunction "PH4(OC4B)_16") (pintype "bidirectional"))
    )
    (net (code "17") (name "/LOCONET") (class "Default")
      (node (ref "JP3") (pin "2") (pinfunction "2_2") (pintype "passive"))
      (node (ref "Q2") (pin "2") (pinfunction "E_2") (pintype "passive"))
      (node (ref "R10") (pin "1") (pinfunction "1_1") (pintype "passive"))
    )
    (net (code "18") (name "/LRESET") (class "Default")
      (node (ref "J5") (pin "7") (pinfunction "7_7") (pintype "passive"))
      (node (ref "R16") (pin "1") (pinfunction "1_1") (pintype "passive"))
    )
    (net (code "19") (name "/MISO") (class "Default")
      (node (ref "SV1") (pin "1") (pinfunction "1_1") (pintype "passive"))
      (node (ref "U5") (pin "22") (pinfunction "(MISO/PCINT3)PB3_22") (pintype "bidirectional"))
      (node (ref "U7") (pin "MISO") (pinfunction "MISO_MISO") (pintype "output"))
    )
    (net (code "20") (name "/MOSI") (class "Default")
      (node (ref "SV1") (pin "4") (pinfunction "4_4") (pintype "passive"))
      (node (ref "U5") (pin "21") (pinfunction "(MOSI/PCINT2)PB2_21") (pintype "bidirectional"))
      (node (ref "U7") (pin "MOSI") (pinfunction "MOSI_MOSI") (pintype "input"))
    )
    (net (code "21") (name "/PS{slash}LOAD") (class "Default")
      (node (ref "J5") (pin "6") (pinfunction "6_6") (pintype "passive"))
      (node (ref "R17") (pin "1") (pinfunction "1_1") (pintype "passive"))
    )
    (net (code "22") (name "/RAILDATA") (class "Default")
      (node (ref "J5") (pin "8") (pinfunction "8_8") (pintype "passive"))
      (node (ref "R14") (pin "1") (pinfunction "1_1") (pintype "passive"))
    )
    (net (code "23") (name "/RAIL_ON{slash}OFF") (class "Default")
      (node (ref "R54") (pin "1") (pinfunction "1_1") (pintype "passive"))
      (node (ref "S2") (pin "2") (pinfunction "S_2") (pintype "passive"))
      (node (ref "U5") (pin "6") (pinfunction "(OC3B/INT4)PE4_6") (pintype "bidirectional"))
    )
    (net (code "24") (name "/RESET") (class "Default")
      (node (ref "C18") (pin "2") (pinfunction "2_2") (pintype "passive"))
      (node (ref "R9") (pin "1") (pinfunction "1_1") (pintype "passive"))
      (node (ref "SJ1") (pin "1") (pinfunction "1_1") (pintype "passive"))
      (node (ref "SV1") (pin "5") (pinfunction "5_5") (pintype "passive"))
      (node (ref "U5") (pin "30") (pinfunction "RESET_30") (pintype "input"))
    )
    (net (code "25") (name "/RXD3") (class "Default")
      (node (ref "JP5") (pin "1") (pinfunction "1_1") (pintype "passive"))
      (node (ref "U5") (pin "63") (pinfunction "PJ0(RXD3/PCINT9)_63") (pintype "bidirectional"))
    )
    (net (code "26") (name "/RXDLED") (class "Default")
      (node (ref "IC5") (pin "22") (pinfunction "CBUS1_22") (pintype "bidirectional"))
      (node (ref "R46") (pin "1") (pinfunction "1_1") (pintype "passive"))
    )
    (net (code "27") (name "/S2") (class "Default")
      (node (ref "R36") (pin "1") (pinfunction "1_1") (pintype "passive"))
      (node (ref "S3") (pin "2") (pinfunction "S_2") (pintype "passive"))
      (node (ref "U5") (pin "17") (pinfunction "PH5(OC4C)_17") (pintype "bidirectional"))
    )
    (net (code "28") (name "/SCK") (class "Default")
      (node (ref "SV1") (pin "3") (pinfunction "3_3") (pintype "passive"))
      (node (ref "U5") (pin "20") (pinfunction "(SCK/PCINT1)PB1_20") (pintype "bidirectional"))
      (node (ref "U7") (pin "SCLK") (pinfunction "SCLK_SCLK") (pintype "bidirectional"))
    )
    (net (code "29") (name "/SCL") (class "Default")
      (node (ref "JP5") (pin "2") (pinfunction "2_2") (pintype "passive"))
      (node (ref "R40") (pin "1") (pinfunction "1_1") (pintype "passive"))
      (node (ref "U5") (pin "43") (pinfunction "(SCL/INT0)PD0_43") (pintype "bidirectional"))
    )
    (net (code "30") (name "/SCLOCK") (class "Default")
      (node (ref "IC2") (pin "4") (pinfunction "A2_4") (pintype "input"))
      (node (ref "U5") (pin "96") (pinfunction "(ADC1)PF1_96") (pintype "bidirectional"))
    )
    (net (code "31") (name "/SDA") (class "Default")
      (node (ref "JP5") (pin "6") (pinfunction "6_6") (pintype "passive"))
      (node (ref "R44") (pin "1") (pinfunction "1_1") (pintype "passive"))
      (node (ref "U5") (pin "44") (pinfunction "(SDA/INT1)PD1_44") (pintype "bidirectional"))
    )
    (net (code "32") (name "/SDATA") (class "Default")
      (node (ref "IC2") (pin "3") (pinfunction "Y4_3") (pintype "tri_state"))
      (node (ref "U5") (pin "97") (pinfunction "(ADC0)PF0_97") (pintype "bidirectional"))
    )
    (net (code "33") (name "/SHORT") (class "Default")
      (node (ref "Q6") (pin "3") (pinfunction "C_3") (pintype "passive"))
      (node (ref "R26") (pin "1") (pinfunction "1_1") (pintype "passive"))
      (node (ref "U5") (pin "5") (pinfunction "(OC3A/AIN1)PE3_5") (pintype "bidirectional"))
    )
    (net (code "34") (name "/SHORT2") (class "Default")
      (node (ref "IC1") (pin "2") (pinfunction "EF_2") (pintype "open_collector"))
      (node (ref "R18") (pin "2") (pinfunction "2_2") (pintype "passive"))
      (node (ref "U5") (pin "51") (pinfunction "(WR)PG0_51") (pintype "bidirectional"))
    )
    (net (code "35") (name "/SPS{slash}LOAD") (class "Default")
      (node (ref "IC2") (pin "6") (pinfunction "A3_6") (pintype "input"))
      (node (ref "U5") (pin "95") (pinfunction "(ADC2)PF2_95") (pintype "bidirectional"))
    )
    (net (code "36") (name "/SRESET") (class "Default")
      (node (ref "IC2") (pin "8") (pinfunction "A4_8") (pintype "input"))
      (node (ref "U5") (pin "94") (pinfunction "(ADC3)PF3_94") (pintype "bidirectional"))
    )
    (net (code "37") (name "/TEMP") (class "Default")
      (node (ref "R48") (pin "2") (pinfunction "2_2") (pintype "passive"))
      (node (ref "R49") (pin "2") (pinfunction "2_2") (pintype "passive"))
      (node (ref "U5") (pin "86") (pinfunction "PK3(ADC11/PCINT19)_86") (pintype "bidirectional"))
    )
    (net (code "38") (name "/TXD3") (class "Default")
      (node (ref "JP5") (pin "3") (pinfunction "3_3") (pintype "passive"))
      (node (ref "U5") (pin "64") (pinfunction "PJ1(TXD3/PCINT10)_64") (pintype "bidirectional"))
    )
    (net (code "39") (name "/TXDLED") (class "Default")
      (node (ref "IC5") (pin "23") (pinfunction "CBUS0_23") (pintype "bidirectional"))
      (node (ref "R47") (pin "1") (pinfunction "1_1") (pintype "passive"))
    )
    (net (code "40") (name "/VBUS") (class "Default")
      (node (ref "L1") (pin "1") (pinfunction "1_1") (pintype "passive"))
      (node (ref "U1") (pin "5") (pinfunction "D4_5") (pintype "passive"))
      (node (ref "U1") (pin "6") (pinfunction "D3_6") (pintype "passive"))
      (node (ref "U1") (pin "7") (pinfunction "D2_7") (pintype "passive"))
      (node (ref "U1") (pin "8") (pinfunction "D1_8") (pintype "passive"))
      (node (ref "U6") (pin "5") (pinfunction "VDD_5") (pintype "bidirectional"))
    )
    (net (code "41") (name "/XNET_RX") (class "Default")
      (node (ref "IC6") (pin "1") (pinfunction "RO_1") (pintype "output"))
      (node (ref "U5") (pin "45") (pinfunction "(RXD1/INT2)PD2_45") (pintype "bidirectional"))
    )
    (net (code "42") (name "/XNET_S{slash}R") (class "Default")
      (node (ref "IC6") (pin "2") (pinfunction "~{RE}_2") (pintype "input"))
      (node (ref "IC6") (pin "3") (pinfunction "DE_3") (pintype "input"))
      (node (ref "U5") (pin "18") (pinfunction "PH6(OC2B)_18") (pintype "bidirectional"))
    )
    (net (code "43") (name "/XNET_TX") (class "Default")
      (node (ref "IC6") (pin "4") (pinfunction "DI_4") (pintype "input"))
      (node (ref "U5") (pin "46") (pinfunction "(TXD1/INT3)PD3_46") (pintype "bidirectional"))
    )
    (net (code "44") (name "/XPA") (class "Default")
      (node (ref "IC6") (pin "6") (pinfunction "A_6") (pintype "bidirectional"))
      (node (ref "J1") (pin "4") (pinfunction "4_4") (pintype "passive"))
      (node (ref "J2") (pin "4") (pinfunction "4_4") (pintype "passive"))
      (node (ref "J3") (pin "4") (pinfunction "4_4") (pintype "passive"))
      (node (ref "JP2") (pin "1") (pinfunction "1_1") (pintype "passive"))
      (node (ref "R12") (pin "1") (pinfunction "1_1") (pintype "passive"))
      (node (ref "Z2") (pin "C") (pinfunction "C_C") (pintype "passive"))
    )
    (net (code "45") (name "/XPB") (class "Default")
      (node (ref "IC6") (pin "7") (pinfunction "B_7") (pintype "bidirectional"))
      (node (ref "J1") (pin "3") (pinfunction "3_3") (pintype "passive"))
      (node (ref "J2") (pin "3") (pinfunction "3_3") (pintype "passive"))
      (node (ref "J3") (pin "3") (pinfunction "3_3") (pintype "passive"))
      (node (ref "R34") (pin "2") (pinfunction "2_2") (pintype "passive"))
      (node (ref "R8") (pin "1") (pinfunction "1_1") (pintype "passive"))
      (node (ref "Z1") (pin "C") (pinfunction "C_C") (pintype "passive"))
    )
    (net (code "46") (name "/~{INT}") (class "Default")
      (node (ref "U5") (pin "24") (pinfunction "(OC1A/PCINT5)PB5_24") (pintype "bidirectional"))
      (node (ref "U7") (pin "INTN") (pinfunction "~{INT}_INTN") (pintype "open_collector"))
    )
    (net (code "47") (name "/~{RST}") (class "Default")
      (node (ref "R20") (pin "1") (pinfunction "1_1") (pintype "passive"))
      (node (ref "SJ1") (pin "2") (pinfunction "2_2") (pintype "passive"))
      (node (ref "U7") (pin "!RST") (pinfunction "~{RST}_!RST") (pintype "input"))
    )
    (net (code "48") (name "CS") (class "Default")
      (node (ref "U5") (pin "23") (pinfunction "(OC2A/PCINT4)PB4_23") (pintype "bidirectional"))
      (node (ref "U7") (pin "!SCN") (pinfunction "~{SCN}_!SCN") (pintype "input"))
    )
    (net (code "49") (name "DCC_STATUS") (class "Default")
      (node (ref "LED5") (pin "A") (pinfunction "A_A") (pintype "passive"))
      (node (ref "U5") (pin "7") (pinfunction "(OC3C/INT5)PE5_7") (pintype "bidirectional"))
    )
    (net (code "50") (name "DTR") (class "Default")
      (node (ref "C18") (pin "1") (pinfunction "1_1") (pintype "passive"))
      (node (ref "IC5") (pin "2") (pinfunction "~{DTR}_2") (pintype "output"))
      (node (ref "J4") (pin "1") (pinfunction "DTR_1") (pintype "passive"))
    )
    (net (code "51") (name "G1") (class "Default")
      (node (ref "IC1") (pin "4") (pinfunction "GND_4") (pintype "power_in"))
      (node (ref "IC1") (pin "8") (pinfunction "GND_8") (pintype "power_in"))
      (node (ref "R43") (pin "2") (pinfunction "2_2") (pintype "passive"))
      (node (ref "U5") (pin "88") (pinfunction "PK1(ADC9/PCINT17)_88") (pintype "bidirectional"))
    )
    (net (code "52") (name "GND") (class "Default")
      (node (ref "B1") (pin "-") (pinfunction "-_-") (pintype "passive"))
      (node (ref "C1") (pin "2") (pinfunction "2_2") (pintype "passive"))
      (node (ref "C10") (pin "-") (pinfunction "-_-") (pintype "passive"))
      (node (ref "C11") (pin "2") (pinfunction "2_2") (pintype "passive"))
      (node (ref "C13") (pin "2") (pinfunction "2_2") (pintype "passive"))
      (node (ref "C14") (pin "1") (pinfunction "1_1") (pintype "passive"))
      (node (ref "C15") (pin "1") (pinfunction "1_1") (pintype "passive"))
      (node (ref "C16") (pin "2") (pinfunction "2_2") (pintype "passive"))
      (node (ref "C17") (pin "2") (pinfunction "2_2") (pintype "passive"))
      (node (ref "C19") (pin "2") (pinfunction "2_2") (pintype "passive"))
      (node (ref "C2") (pin "2") (pinfunction "2_2") (pintype "passive"))
      (node (ref "C20") (pin "2") (pinfunction "2_2") (pintype "passive"))
      (node (ref "C21") (pin "2") (pinfunction "2_2") (pintype "passive"))
      (node (ref "C22") (pin "2") (pinfunction "2_2") (pintype "passive"))
      (node (ref "C23") (pin "2") (pinfunction "2_2") (pintype "passive"))
      (node (ref "C24") (pin "2") (pinfunction "2_2") (pintype "passive"))
      (node (ref "C25") (pin "1") (pinfunction "1_1") (pintype "passive"))
      (node (ref "C26") (pin "2") (pinfunction "2_2") (pintype "passive"))
      (node (ref "C27") (pin "2") (pinfunction "2_2") (pintype "passive"))
      (node (ref "C28") (pin "-") (pinfunction "-_-") (pintype "passive"))
      (node (ref "C29") (pin "2") (pinfunction "2_2") (pintype "passive"))
      (node (ref "C3") (pin "-") (pinfunction "-_-") (pintype "passive"))
      (node (ref "C4") (pin "2") (pinfunction "2_2") (pintype "passive"))
      (node (ref "C5") (pin "2") (pinfunction "2_2") (pintype "passive"))
      (node (ref "C6") (pin "2") (pinfunction "2_2") (pintype "passive"))
      (node (ref "C7") (pin "2") (pinfunction "2_2") (pintype "passive"))
      (node (ref "C8") (pin "2") (pinfunction "2_2") (pintype "passive"))
      (node (ref "C9") (pin "2") (pinfunction "2_2") (pintype "passive"))
      (node (ref "IC2") (pin "1") (pinfunction "G_1") (pintype "input"))
      (node (ref "IC2") (pin "10") (pinfunction "GND_10") (pintype "power_in"))
      (node (ref "IC2") (pin "19") (pinfunction "G_19") (pintype "input"))
      (node (ref "IC3") (pin "4") (pinfunction "V-_4") (pintype "power_in"))
      (node (ref "IC4") (pin "GND") (pinfunction "GND_GND") (pintype "input"))
      (node (ref "IC5") (pin "18") (pinfunction "GND_18") (pintype "power_in"))
      (node (ref "IC5") (pin "21") (pinfunction "GND_21") (pintype "power_in"))
      (node (ref "IC5") (pin "25") (pinfunction "GND_25") (pintype "power_in"))
      (node (ref "IC5") (pin "26") (pinfunction "TEST_26") (pintype "input"))
      (node (ref "IC5") (pin "7") (pinfunction "GND_7") (pintype "power_in"))
      (node (ref "IC6") (pin "5") (pinfunction "GND_5") (pintype "input"))
      (node (ref "J1") (pin "2") (pinfunction "2_2") (pintype "passive"))
      (node (ref "J2") (pin "2") (pinfunction "2_2") (pintype "passive"))
      (node (ref "J3") (pin "2") (pinfunction "2_2") (pintype "passive"))
      (node (ref "J4") (pin "6") (pinfunction "GND_6") (pintype "passive"))
      (node (ref "J5") (pin "3") (pinfunction "3_3") (pintype "passive"))
      (node (ref "J5") (pin "5") (pinfunction "5_5") (pintype "passive"))
      (node (ref "J6") (pin "GND") (pinfunction "GND_GND") (pintype "power_in"))
      (node (ref "J6") (pin "S1") (pinfunction "SHIELD_S1") (pintype "bidirectional"))
      (node (ref "J6") (pin "S2") (pinfunction "SHIELD_S2") (pintype "bidirectional"))
      (node (ref "J6") (pin "S3") (pinfunction "SHIELD_S3") (pintype "bidirectional"))
      (node (ref "J6") (pin "S4") (pinfunction "SHIELD_S4") (pintype "bidirectional"))
      (node (ref "J7") (pin "2") (pinfunction "2_2") (pintype "passive"))
      (node (ref "J7") (pin "5") (pinfunction "5_5") (pintype "passive"))
      (node (ref "JP5") (pin "4") (pinfunction "4_4") (pintype "passive"))
      (node (ref "JP5") (pin "9") (pinfunction "9_9") (pintype "passive"))
      (node (ref "Q1") (pin "2") (pinfunction "E_2") (pintype "passive"))
      (node (ref "Q10") (pin "2") (pinfunction "E_2") (pintype "passive"))
      (node (ref "Q11") (pin "2") (pinfunction "E_2") (pintype "passive"))
      (node (ref "Q4") (pin "2") (pinfunction "E_2") (pintype "passive"))
      (node (ref "Q6") (pin "2") (pinfunction "E_2") (pintype "passive"))
      (node (ref "Q7") (pin "2") (pinfunction "E_2") (pintype "passive"))
      (node (ref "R30") (pin "1") (pinfunction "1_1") (pintype "passive"))
      (node (ref "R31") (pin "2") (pinfunction "2_2") (pintype "passive"))
      (node (ref "R33") (pin "2") (pinfunction "2_2") (pintype "passive"))
      (node (ref "R34") (pin "1") (pinfunction "1_1") (pintype "passive"))
      (node (ref "R35") (pin "1") (pinfunction "1_1") (pintype "passive"))
      (node (ref "R37") (pin "2") (pinfunction "2_2") (pintype "passive"))
      (node (ref "R4") (pin "2") (pinfunction "2_2") (pintype "passive"))
      (node (ref "R43") (pin "1") (pinfunction "1_1") (pintype "passive"))
      (node (ref "R49") (pin "1") (pinfunction "1_1") (pintype "passive"))
      (node (ref "R50") (pin "1") (pinfunction "1_1") (pintype "passive"))
      (node (ref "R51") (pin "1") (pinfunction "1_1") (pintype "passive"))
      (node (ref "R52") (pin "1") (pinfunction "1_1") (pintype "passive"))
      (node (ref "R6") (pin "1") (pinfunction "1_1") (pintype "passive"))
      (node (ref "R7") (pin "1") (pinfunction "1_1") (pintype "passive"))
      (node (ref "S2") (pin "1") (pinfunction "P_1") (pintype "passive"))
      (node (ref "S3") (pin "1") (pinfunction "P_1") (pintype "passive"))
      (node (ref "SV1") (pin "6") (pinfunction "6_6") (pintype "passive"))
      (node (ref "U$1") (pin "A1") (pinfunction "GND_A1") (pintype "power_in"))
      (node (ref "U$2") (pin "RING") (pinfunction "RING_RING") (pintype "bidirectional"))
      (node (ref "U$2") (pin "RING_SW") (pinfunction "RING_SW_RING_SW") (pintype "bidirectional"))
      (node (ref "U2") (pin "4") (pinfunction "ADJ_4") (pintype "input"))
      (node (ref "U3") (pin "1") (pinfunction "ADJ_1") (pintype "input"))
      (node (ref "U4") (pin "4") (pinfunction "ADJ_4") (pintype "input"))
      (node (ref "U5") (pin "11") (pinfunction "GND_11") (pintype "power_in"))
      (node (ref "U5") (pin "32") (pinfunction "GND1_32") (pintype "power_in"))
      (node (ref "U5") (pin "62") (pinfunction "GND2_62") (pintype "power_in"))
      (node (ref "U5") (pin "81") (pinfunction "GND3_81") (pintype "power_in"))
      (node (ref "U5") (pin "99") (pinfunction "AGND_99") (pintype "power_in"))
      (node (ref "U6") (pin "2") (pinfunction "GND_2") (pintype "bidirectional"))
      (node (ref "U7") (pin "GND1") (pinfunction "GND1_GND1") (pintype "passive"))
      (node (ref "U7") (pin "GND2") (pinfunction "GND2_GND2") (pintype "passive"))
      (node (ref "U7") (pin "GND3") (pinfunction "GND3_GND3") (pintype "passive"))
      (node (ref "Z1") (pin "A") (pinfunction "A_A") (pintype "passive"))
      (node (ref "Z2") (pin "A") (pinfunction "A_A") (pintype "passive"))
      (node (ref "Z3") (pin "A") (pinfunction "A_A") (pintype "passive"))
      (node (ref "Z4") (pin "A") (pinfunction "A_A") (pintype "passive"))
    )
    (net (code "53") (name "LN_RECEIVE") (class "Default")
      (node (ref "Q11") (pin "3") (pinfunction "C_3") (pintype "passive"))
      (node (ref "R42") (pin "1") (pinfunction "1_1") (pintype "passive"))
      (node (ref "U5") (pin "36") (pinfunction "PL1(ICP5)_36") (pintype "bidirectional"))
    )
    (net (code "54") (name "Net-(D2-PadA)") (class "Default")
      (node (ref "D2") (pin "A") (pinfunction "A_A") (pintype "passive"))
      (node (ref "J1") (pin "5") (pinfunction "5_5") (pintype "passive"))
    )
    (net (code "55") (name "Net-(D2-PadC)") (class "Default")
      (node (ref "D2") (pin "C") (pinfunction "C_C") (pintype "passive"))
      (node (ref "R22") (pin "1") (pinfunction "1_1") (pintype "passive"))
      (node (ref "R23") (pin "1") (pinfunction "1_1") (pintype "passive"))
    )
    (net (code "56") (name "Net-(D5-A)") (class "Default")
      (node (ref "D5") (pin "1") (pinfunction "A_1") (pintype "passive"))
      (node (ref "Q9") (pin "1") (pinfunction "G_1") (pintype "passive"))
      (node (ref "R31") (pin "1") (pinfunction "1_1") (pintype "passive"))
    )
    (net (code "57") (name "Net-(F2-Pad1)") (class "Default")
      (node (ref "F2") (pin "1") (pinfunction "1_1") (pintype "passive"))
      (node (ref "J5") (pin "1") (pinfunction "1_1") (pintype "passive"))
      (node (ref "Z3") (pin "C") (pinfunction "C_C") (pintype "passive"))
    )
    (net (code "58") (name "Net-(IC1-OUT1)") (class "Default")
      (node (ref "C12") (pin "2") (pinfunction "2_2") (pintype "passive"))
      (node (ref "C13") (pin "1") (pinfunction "1_1") (pintype "passive"))
      (node (ref "IC1") (pin "1") (pinfunction "OUT1_1") (pintype "output"))
      (node (ref "K1") (pin "P") (pinfunction "P_P") (pintype "passive"))
    )
    (net (code "59") (name "Net-(IC1-OUT2)") (class "Default")
      (node (ref "C12") (pin "1") (pinfunction "1_1") (pintype "passive"))
      (node (ref "C16") (pin "1") (pinfunction "1_1") (pintype "passive"))
      (node (ref "IC1") (pin "7") (pinfunction "OUT2_7") (pintype "output"))
      (node (ref "X9") (pin "1") (pinfunction "1_1") (pintype "passive"))
      (node (ref "X9") (pin "3") (pinfunction "1_3") (pintype "passive"))
    )
    (net (code "60") (name "Net-(IC2A-Y2)") (class "Default")
      (node (ref "IC2") (pin "16") (pinfunction "Y2_16") (pintype "tri_state"))
      (node (ref "R15") (pin "2") (pinfunction "2_2") (pintype "passive"))
    )
    (net (code "61") (name "Net-(IC2A-Y3)") (class "Default")
      (node (ref "IC2") (pin "14") (pinfunction "Y3_14") (pintype "tri_state"))
      (node (ref "R17") (pin "2") (pinfunction "2_2") (pintype "passive"))
    )
    (net (code "62") (name "Net-(IC2A-Y4)") (class "Default")
      (node (ref "IC2") (pin "12") (pinfunction "Y4_12") (pintype "tri_state"))
      (node (ref "R16") (pin "2") (pinfunction "2_2") (pintype "passive"))
    )
    (net (code "63") (name "Net-(IC2B-A4)") (class "Default")
      (node (ref "IC2") (pin "17") (pinfunction "A4_17") (pintype "input"))
      (node (ref "R13") (pin "1") (pinfunction "1_1") (pintype "passive"))
      (node (ref "R37") (pin "1") (pinfunction "1_1") (pintype "passive"))
    )
    (net (code "64") (name "Net-(IC2B-Y1)") (class "Default")
      (node (ref "IC2") (pin "9") (pinfunction "Y1_9") (pintype "tri_state"))
      (node (ref "R14") (pin "2") (pinfunction "2_2") (pintype "passive"))
    )
    (net (code "65") (name "Net-(IC3A-+IN)") (class "Default")
      (node (ref "IC3") (pin "3") (pinfunction "+IN_3") (pintype "input"))
      (node (ref "R52") (pin "2") (pinfunction "2_2") (pintype "passive"))
      (node (ref "R53") (pin "1") (pinfunction "1_1") (pintype "passive"))
    )
    (net (code "66") (name "Net-(IC3A-OUT)") (class "Default")
      (node (ref "IC3") (pin "1") (pinfunction "OUT_1") (pintype "output"))
      (node (ref "U1") (pin "4") (pinfunction "G_4") (pintype "passive"))
    )
    (net (code "67") (name "Net-(IC5-3V3OUT)") (class "Default")
      (node (ref "IC5") (pin "17") (pinfunction "3V3OUT_17") (pintype "output"))
      (node (ref "SJ2") (pin "1") (pinfunction "1_1") (pintype "passive"))
    )
    (net (code "68") (name "Net-(IC5-USBDM)") (class "Default")
      (node (ref "IC5") (pin "16") (pinfunction "USBDM_16") (pintype "bidirectional"))
      (node (ref "U6") (pin "6") (pinfunction "IO1O_6") (pintype "bidirectional"))
    )
    (net (code "69") (name "Net-(IC5-USBDP)") (class "Default")
      (node (ref "IC5") (pin "15") (pinfunction "USBDP_15") (pintype "bidirectional"))
      (node (ref "U6") (pin "4") (pinfunction "IO2O_4") (pintype "bidirectional"))
    )
    (net (code "70") (name "Net-(IC5-VCCIO)") (class "Default")
      (node (ref "IC5") (pin "4") (pinfunction "VCCIO_4") (pintype "power_in"))
      (node (ref "SJ2") (pin "2") (pinfunction "2_2") (pintype "passive"))
    )
    (net (code "71") (name "Net-(J1-Pad6)") (class "Default")
      (node (ref "J1") (pin "6") (pinfunction "6_6") (pintype "passive"))
      (node (ref "R5") (pin "1") (pinfunction "1_1") (pintype "passive"))
    )
    (net (code "72") (name "Net-(J6-PadVBUS)") (class "Default")
      (node (ref "J6") (pin "VBUS") (pinfunction "VBUS_VBUS") (pintype "power_in"))
      (node (ref "L1") (pin "2") (pinfunction "2_2") (pintype "passive"))
    )
    (net (code "73") (name "Net-(JP2-Pad2)") (class "Default")
      (node (ref "JP2") (pin "2") (pinfunction "2_2") (pintype "passive"))
      (node (ref "R8") (pin "2") (pinfunction "2_2") (pintype "passive"))
    )
    (net (code "74") (name "Net-(LED1-C)") (class "Default")
      (node (ref "LED1") (pin "K") (pinfunction "C_K") (pintype "passive"))
      (node (ref "R7") (pin "2") (pinfunction "2_2") (pintype "passive"))
    )
    (net (code "75") (name "Net-(LED2-C)") (class "Default")
      (node (ref "LED2") (pin "K") (pinfunction "C_K") (pintype "passive"))
      (node (ref "R46") (pin "2") (pinfunction "2_2") (pintype "passive"))
    )
    (net (code "76") (name "Net-(LED3-C)") (class "Default")
      (node (ref "LED3") (pin "K") (pinfunction "C_K") (pintype "passive"))
      (node (ref "R47") (pin "2") (pinfunction "2_2") (pintype "passive"))
    )
    (net (code "77") (name "Net-(LED4-C)") (class "Default")
      (node (ref "LED4") (pin "K") (pinfunction "C_K") (pintype "passive"))
      (node (ref "R35") (pin "2") (pinfunction "2_2") (pintype "passive"))
    )
    (net (code "78") (name "Net-(LED5-C)") (class "Default")
      (node (ref "LED5") (pin "K") (pinfunction "C_K") (pintype "passive"))
      (node (ref "R6") (pin "2") (pinfunction "2_2") (pintype "passive"))
    )
    (net (code "79") (name "Net-(LED6-C)") (class "Default")
      (node (ref "LED6") (pin "K") (pinfunction "C_K") (pintype "passive"))
      (node (ref "R51") (pin "2") (pinfunction "2_2") (pintype "passive"))
    )
    (net (code "80") (name "Net-(LED7-C)") (class "Default")
      (node (ref "LED7") (pin "K") (pinfunction "C_K") (pintype "passive"))
      (node (ref "R50") (pin "2") (pinfunction "2_2") (pintype "passive"))
    )
    (net (code "81") (name "Net-(Q1-B)") (class "Default")
      (node (ref "Q1") (pin "1") (pinfunction "B_1") (pintype "passive"))
      (node (ref "R3") (pin "1") (pinfunction "1_1") (pintype "passive"))
    )
    (net (code "82") (name "Net-(Q1-C)") (class "Default")
      (node (ref "J7") (pin "3") (pinfunction "3_3") (pintype "passive"))
      (node (ref "J7") (pin "4") (pinfunction "4_4") (pintype "passive"))
      (node (ref "JP3") (pin "1") (pinfunction "1_1") (pintype "passive"))
      (node (ref "Q1") (pin "3") (pinfunction "C_3") (pintype "passive"))
      (node (ref "R2") (pin "1") (pinfunction "1_1") (pintype "passive"))
      (node (ref "R41") (pin "2") (pinfunction "2_2") (pintype "passive"))
    )
    (net (code "83") (name "Net-(Q2-B)") (class "Default")
      (node (ref "Q2") (pin "1") (pinfunction "B_1") (pintype "passive"))
      (node (ref "Q3") (pin "2") (pinfunction "E_2") (pintype "passive"))
      (node (ref "R10") (pin "2") (pinfunction "2_2") (pintype "passive"))
    )
    (net (code "84") (name "Net-(Q2-C)") (class "Default")
      (node (ref "Q2") (pin "3") (pinfunction "C_3") (pintype "passive"))
      (node (ref "Q3") (pin "1") (pinfunction "B_1") (pintype "passive"))
      (node (ref "R11") (pin "1") (pinfunction "1_1") (pintype "passive"))
    )
    (net (code "85") (name "Net-(Q4-B)") (class "Default")
      (node (ref "Q4") (pin "1") (pinfunction "B_1") (pintype "passive"))
      (node (ref "R24") (pin "1") (pinfunction "1_1") (pintype "passive"))
    )
    (net (code "86") (name "Net-(Q4-C)") (class "Default")
      (node (ref "Q4") (pin "3") (pinfunction "C_3") (pintype "passive"))
      (node (ref "Q5") (pin "2") (pinfunction "E_2") (pintype "passive"))
      (node (ref "R23") (pin "2") (pinfunction "2_2") (pintype "passive"))
    )
    (net (code "87") (name "Net-(Q5-B)") (class "Default")
      (node (ref "Q5") (pin "1") (pinfunction "B_1") (pintype "passive"))
      (node (ref "R25") (pin "1") (pinfunction "1_1") (pintype "passive"))
    )
    (net (code "88") (name "Net-(Q5-C)") (class "Default")
      (node (ref "J1") (pin "1") (pinfunction "1_1") (pintype "passive"))
      (node (ref "Q5") (pin "3") (pinfunction "C_3") (pintype "passive"))
      (node (ref "R22") (pin "2") (pinfunction "2_2") (pintype "passive"))
    )
    (net (code "89") (name "Net-(Q6-B)") (class "Default")
      (node (ref "Q6") (pin "1") (pinfunction "B_1") (pintype "passive"))
      (node (ref "R5") (pin "2") (pinfunction "2_2") (pintype "passive"))
    )
    (net (code "90") (name "Net-(Q7-B)") (class "Default")
      (node (ref "Q7") (pin "1") (pinfunction "B_1") (pintype "passive"))
      (node (ref "R1") (pin "1") (pinfunction "1_1") (pintype "passive"))
    )
    (net (code "91") (name "Net-(Q7-C)") (class "Default")
      (node (ref "D7") (pin "A") (pinfunction "A_A") (pintype "passive"))
      (node (ref "JP1") (pin "2") (pinfunction "2_2") (pintype "passive"))
      (node (ref "Q7") (pin "3") (pinfunction "C_3") (pintype "passive"))
      (node (ref "R28") (pin "2") (pinfunction "2_2") (pintype "passive"))
    )
    (net (code "92") (name "Net-(Q9-D)") (class "Default")
      (node (ref "Q9") (pin "3") (pinfunction "D_3") (pintype "passive"))
      (node (ref "U$2") (pin "TIP") (pinfunction "TIP_TIP") (pintype "bidirectional"))
    )
    (net (code "93") (name "Net-(Q10-B)") (class "Default")
      (node (ref "Q10") (pin "1") (pinfunction "B_1") (pintype "passive"))
      (node (ref "R45") (pin "1") (pinfunction "1_1") (pintype "passive"))
    )
    (net (code "94") (name "Net-(Q10-C)") (class "Default")
      (node (ref "D4") (pin "A") (pinfunction "A_A") (pintype "passive"))
      (node (ref "K1") (pin "2") (pinfunction "2_2") (pintype "passive"))
      (node (ref "Q10") (pin "3") (pinfunction "C_3") (pintype "passive"))
    )
    (net (code "95") (name "Net-(Q11-B)") (class "Default")
      (node (ref "Q11") (pin "1") (pinfunction "B_1") (pintype "passive"))
      (node (ref "R41") (pin "1") (pinfunction "1_1") (pintype "passive"))
    )
    (net (code "96") (name "Net-(U$1-GPIO0)") (class "Default")
      (node (ref "R32") (pin "2") (pinfunction "2_2") (pintype "passive"))
      (node (ref "U$1") (pin "C1") (pinfunction "GPIO0_C1") (pintype "bidirectional"))
    )
    (net (code "97") (name "Net-(U$1-RST)") (class "Default")
      (node (ref "R29") (pin "2") (pinfunction "2_2") (pintype "passive"))
      (node (ref "U$1") (pin "C2") (pinfunction "RST_C2") (pintype "bidirectional"))
    )
    (net (code "98") (name "Net-(U$1-URXD)") (class "Default")
      (node (ref "R33") (pin "1") (pinfunction "1_1") (pintype "passive"))
      (node (ref "R38") (pin "2") (pinfunction "2_2") (pintype "passive"))
      (node (ref "U$1") (pin "D1") (pinfunction "URXD_D1") (pintype "bidirectional"))
    )
    (net (code "99") (name "Net-(U5-AREF)") (class "Default")
      (node (ref "C25") (pin "2") (pinfunction "2_2") (pintype "passive"))
      (node (ref "U5") (pin "98") (pinfunction "AREF_98") (pintype "bidirectional"))
    )
    (net (code "100") (name "Net-(U5-XTAL1)") (class "Default")
      (node (ref "C15") (pin "2") (pinfunction "2_2") (pintype "passive"))
      (node (ref "U5") (pin "34") (pinfunction "XTAL1_34") (pintype "input"))
      (node (ref "Y1") (pin "1") (pinfunction "1_1") (pintype "passive"))
    )
    (net (code "101") (name "Net-(U5-XTAL2)") (class "Default")
      (node (ref "C14") (pin "2") (pinfunction "2_2") (pintype "passive"))
      (node (ref "U5") (pin "33") (pinfunction "XTAL2_33") (pintype "output"))
      (node (ref "Y1") (pin "2") (pinfunction "2_2") (pintype "passive"))
    )
    (net (code "102") (name "Net-(U6-IO1I)") (class "Default")
      (node (ref "J6") (pin "D-") (pinfunction "D-_D-") (pintype "bidirectional"))
      (node (ref "U6") (pin "1") (pinfunction "IO1I_1") (pintype "bidirectional"))
    )
    (net (code "103") (name "Net-(U6-IO2I)") (class "Default")
      (node (ref "J6") (pin "D+") (pinfunction "D+_D+") (pintype "bidirectional"))
      (node (ref "U6") (pin "3") (pinfunction "IO2I_3") (pintype "bidirectional"))
    )
    (net (code "104") (name "Net-(X9B-1)") (class "Default")
      (node (ref "K1") (pin "S") (pinfunction "S_S") (pintype "passive"))
      (node (ref "X9") (pin "2") (pinfunction "1_2") (pintype "passive"))
    )
    (net (code "105") (name "Net-(X9D-1)") (class "Default")
      (node (ref "K1") (pin "O") (pinfunction "O_O") (pintype "passive"))
      (node (ref "X9") (pin "4") (pinfunction "1_4") (pintype "passive"))
    )
    (net (code "106") (name "Net-(X9E-1)") (class "Default")
      (node (ref "B1") (pin "AC1") (pinfunction "AC1_AC1") (pintype "passive"))
      (node (ref "X9") (pin "5") (pinfunction "1_5") (pintype "passive"))
    )
    (net (code "107") (name "Net-(X9F-1)") (class "Default")
      (node (ref "B1") (pin "AC2") (pinfunction "AC2_AC2") (pintype "passive"))
      (node (ref "X9") (pin "6") (pinfunction "1_6") (pintype "passive"))
    )
    (net (code "108") (name "PROG") (class "Default")
      (node (ref "R45") (pin "2") (pinfunction "2_2") (pintype "passive"))
      (node (ref "U5") (pin "92") (pinfunction "(ADC5/TMS)PF5_92") (pintype "bidirectional"))
    )
    (net (code "109") (name "RXD") (class "Default")
      (node (ref "IC5") (pin "1") (pinfunction "TXD_1") (pintype "output"))
      (node (ref "J4") (pin "3") (pinfunction "TXO_3") (pintype "passive"))
      (node (ref "U5") (pin "2") (pinfunction "(RXD0/PCIN8)PE0_2") (pintype "bidirectional"))
    )
    (net (code "110") (name "SSHORT") (class "Default")
      (node (ref "LED4") (pin "A") (pinfunction "A_A") (pintype "passive"))
      (node (ref "U5") (pin "39") (pinfunction "PL4(OC5B)_39") (pintype "bidirectional"))
    )
    (net (code "111") (name "TXD") (class "Default")
      (node (ref "IC5") (pin "5") (pinfunction "RXD_5") (pintype "input"))
      (node (ref "J4") (pin "2") (pinfunction "RXI_2") (pintype "passive"))
      (node (ref "U5") (pin "3") (pinfunction "(TXD0)PE1_3") (pintype "bidirectional"))
    )
    (net (code "112") (name "VCCIO") (class "Default")
      (node (ref "C7") (pin "1") (pinfunction "1_1") (pintype "passive"))
      (node (ref "D7") (pin "C") (pinfunction "C_C") (pintype "passive"))
      (node (ref "F1") (pin "1") (pinfunction "1_1") (pintype "passive"))
      (node (ref "J2") (pin "5") (pinfunction "5_5") (pintype "passive"))
      (node (ref "J3") (pin "5") (pinfunction "5_5") (pintype "passive"))
      (node (ref "J7") (pin "1") (pinfunction "1_1") (pintype "passive"))
      (node (ref "J7") (pin "6") (pinfunction "6_6") (pintype "passive"))
      (node (ref "JP1") (pin "1") (pinfunction "1_1") (pintype "passive"))
      (node (ref "Q3") (pin "3") (pinfunction "C_3") (pintype "passive"))
      (node (ref "R11") (pin "2") (pinfunction "2_2") (pintype "passive"))
      (node (ref "R28") (pin "1") (pinfunction "1_1") (pintype "passive"))
      (node (ref "Z4") (pin "C") (pinfunction "C_C") (pintype "passive"))
    )
    (net (code "113") (name "WRXD") (class "Default")
      (node (ref "R38") (pin "1") (pinfunction "1_1") (pintype "passive"))
      (node (ref "R39") (pin "2") (pinfunction "2_2") (pintype "passive"))
      (node (ref "U5") (pin "13") (pinfunction "PH1(TXD2)_13") (pintype "bidirectional"))
    )
    (net (code "114") (name "WTXD") (class "Default")
      (node (ref "U$1") (pin "A2") (pinfunction "UTXD_A2") (pintype "bidirectional"))
      (node (ref "U5") (pin "12") (pinfunction "PH0(RXD2)_12") (pintype "bidirectional"))
    )
    (net (code "115") (name "unconnected-(IC2A-A1-Pad2)") (class "Default")
      (node (ref "IC2") (pin "2") (pinfunction "A1_2") (pintype "input"))
    )
    (net (code "116") (name "unconnected-(IC2A-Y1-Pad18)") (class "Default")
      (node (ref "IC2") (pin "18") (pinfunction "Y1_18") (pintype "tri_state"))
    )
    (net (code "117") (name "unconnected-(IC2B-A2-Pad13)") (class "Default")
      (node (ref "IC2") (pin "13") (pinfunction "A2_13") (pintype "input"))
    )
    (net (code "118") (name "unconnected-(IC2B-A3-Pad15)") (class "Default")
      (node (ref "IC2") (pin "15") (pinfunction "A3_15") (pintype "input"))
    )
    (net (code "119") (name "unconnected-(IC2B-Y2-Pad7)") (class "Default")
      (node (ref "IC2") (pin "7") (pinfunction "Y2_7") (pintype "tri_state"))
    )
    (net (code "120") (name "unconnected-(IC2B-Y3-Pad5)") (class "Default")
      (node (ref "IC2") (pin "5") (pinfunction "Y3_5") (pintype "tri_state"))
    )
    (net (code "121") (name "unconnected-(IC3B-+IN-Pad5)") (class "Default")
      (node (ref "IC3") (pin "5") (pinfunction "+IN_5") (pintype "input"))
    )
    (net (code "122") (name "unconnected-(IC3B--IN-Pad6)") (class "Default")
      (node (ref "IC3") (pin "6") (pinfunction "-IN_6") (pintype "input"))
    )
    (net (code "123") (name "unconnected-(IC3B-OUT-Pad7)") (class "Default")
      (node (ref "IC3") (pin "7") (pinfunction "OUT_7") (pintype "output"))
    )
    (net (code "124") (name "unconnected-(IC5-CBUS2-Pad13)") (class "Default")
      (node (ref "IC5") (pin "13") (pinfunction "CBUS2_13") (pintype "bidirectional"))
    )
    (net (code "125") (name "unconnected-(IC5-CBUS3-Pad14)") (class "Default")
      (node (ref "IC5") (pin "14") (pinfunction "CBUS3_14") (pintype "bidirectional"))
    )
    (net (code "126") (name "unconnected-(IC5-CBUS4-Pad12)") (class "Default")
      (node (ref "IC5") (pin "12") (pinfunction "CBUS4_12") (pintype "bidirectional"))
    )
    (net (code "127") (name "unconnected-(IC5-OSCI-Pad27)") (class "Default")
      (node (ref "IC5") (pin "27") (pinfunction "OSCI_27") (pintype "input"))
    )
    (net (code "128") (name "unconnected-(IC5-OSCO-Pad28)") (class "Default")
      (node (ref "IC5") (pin "28") (pinfunction "OSCO_28") (pintype "output"))
    )
    (net (code "129") (name "unconnected-(IC5-~{CTS}-Pad11)") (class "Default")
      (node (ref "IC5") (pin "11") (pinfunction "~{CTS}_11") (pintype "input"))
    )
    (net (code "130") (name "unconnected-(IC5-~{DCD}-Pad10)") (class "Default")
      (node (ref "IC5") (pin "10") (pinfunction "~{DCD}_10") (pintype "input"))
    )
    (net (code "131") (name "unconnected-(IC5-~{DSR}-Pad9)") (class "Default")
      (node (ref "IC5") (pin "9") (pinfunction "~{DSR}_9") (pintype "input"))
    )
    (net (code "132") (name "unconnected-(IC5-~{RESET}-Pad19)") (class "Default")
      (node (ref "IC5") (pin "19") (pinfunction "~{RESET}_19") (pintype "input"))
    )
    (net (code "133") (name "unconnected-(IC5-~{RI}-Pad6)") (class "Default")
      (node (ref "IC5") (pin "6") (pinfunction "~{RI}_6") (pintype "input"))
    )
    (net (code "134") (name "unconnected-(IC5-~{RTS}-Pad3)") (class "Default")
      (node (ref "IC5") (pin "3") (pinfunction "~{RTS}_3") (pintype "output"))
    )
    (net (code "135") (name "unconnected-(J2-Pad1)") (class "Default")
      (node (ref "J2") (pin "1") (pinfunction "1_1") (pintype "passive"))
    )
    (net (code "136") (name "unconnected-(J2-Pad6)") (class "Default")
      (node (ref "J2") (pin "6") (pinfunction "6_6") (pintype "passive"))
    )
    (net (code "137") (name "unconnected-(J3-Pad1)") (class "Default")
      (node (ref "J3") (pin "1") (pinfunction "1_1") (pintype "passive"))
    )
    (net (code "138") (name "unconnected-(J3-Pad6)") (class "Default")
      (node (ref "J3") (pin "6") (pinfunction "6_6") (pintype "passive"))
    )
    (net (code "139") (name "unconnected-(J4-CTS-Pad5)") (class "Default")
      (node (ref "J4") (pin "5") (pinfunction "CTS_5") (pintype "passive"))
    )
    (net (code "140") (name "unconnected-(J6-PadID)") (class "Default")
      (node (ref "J6") (pin "ID") (pinfunction "ID_ID") (pintype "bidirectional"))
    )
    (net (code "141") (name "unconnected-(JP5-Pad8)") (class "Default")
      (node (ref "JP5") (pin "8") (pinfunction "8_8") (pintype "passive"))
    )
    (net (code "142") (name "unconnected-(U$1-GPIO2-PadB1)") (class "Default")
      (node (ref "U$1") (pin "B1") (pinfunction "GPIO2_B1") (pintype "bidirectional"))
    )
    (net (code "143") (name "unconnected-(U5-(A8)PC0-Pad53)") (class "Default")
      (node (ref "U5") (pin "53") (pinfunction "(A8)PC0_53") (pintype "bidirectional"))
    )
    (net (code "144") (name "unconnected-(U5-(A9)PC1-Pad54)") (class "Default")
      (node (ref "U5") (pin "54") (pinfunction "(A9)PC1_54") (pintype "bidirectional"))
    )
    (net (code "145") (name "unconnected-(U5-(A10)PC2-Pad55)") (class "Default")
      (node (ref "U5") (pin "55") (pinfunction "(A10)PC2_55") (pintype "bidirectional"))
    )
    (net (code "146") (name "unconnected-(U5-(A11)PC3-Pad56)") (class "Default")
      (node (ref "U5") (pin "56") (pinfunction "(A11)PC3_56") (pintype "bidirectional"))
    )
    (net (code "147") (name "unconnected-(U5-(A12)PC4-Pad57)") (class "Default")
      (node (ref "U5") (pin "57") (pinfunction "(A12)PC4_57") (pintype "bidirectional"))
    )
    (net (code "148") (name "unconnected-(U5-(A13)PC5-Pad58)") (class "Default")
      (node (ref "U5") (pin "58") (pinfunction "(A13)PC5_58") (pintype "bidirectional"))
    )
    (net (code "149") (name "unconnected-(U5-(A14)PC6-Pad59)") (class "Default")
      (node (ref "U5") (pin "59") (pinfunction "(A14)PC6_59") (pintype "bidirectional"))
    )
    (net (code "150") (name "unconnected-(U5-(A15)PC7-Pad60)") (class "Default")
      (node (ref "U5") (pin "60") (pinfunction "(A15)PC7_60") (pintype "bidirectional"))
    )
    (net (code "151") (name "unconnected-(U5-(AD0)PA0-Pad78)") (class "Default")
      (node (ref "U5") (pin "78") (pinfunction "(AD0)PA0_78") (pintype "bidirectional"))
    )
    (net (code "152") (name "unconnected-(U5-(AD1)PA1-Pad77)") (class "Default")
      (node (ref "U5") (pin "77") (pinfunction "(AD1)PA1_77") (pintype "bidirectional"))
    )
    (net (code "153") (name "unconnected-(U5-(AD2)PA2-Pad76)") (class "Default")
      (node (ref "U5") (pin "76") (pinfunction "(AD2)PA2_76") (pintype "bidirectional"))
    )
    (net (code "154") (name "unconnected-(U5-(AD3)PA3-Pad75)") (class "Default")
      (node (ref "U5") (pin "75") (pinfunction "(AD3)PA3_75") (pintype "bidirectional"))
    )
    (net (code "155") (name "unconnected-(U5-(AD4)PA4-Pad74)") (class "Default")
      (node (ref "U5") (pin "74") (pinfunction "(AD4)PA4_74") (pintype "bidirectional"))
    )
    (net (code "156") (name "unconnected-(U5-(AD5)PA5-Pad73)") (class "Default")
      (node (ref "U5") (pin "73") (pinfunction "(AD5)PA5_73") (pintype "bidirectional"))
    )
    (net (code "157") (name "unconnected-(U5-(AD6)PA6-Pad72)") (class "Default")
      (node (ref "U5") (pin "72") (pinfunction "(AD6)PA6_72") (pintype "bidirectional"))
    )
    (net (code "158") (name "unconnected-(U5-(AD7)PA7-Pad71)") (class "Default")
      (node (ref "U5") (pin "71") (pinfunction "(AD7)PA7_71") (pintype "bidirectional"))
    )
    (net (code "159") (name "unconnected-(U5-(ADC6{slash}TDO)PF6-Pad91)") (class "Default")
      (node (ref "U5") (pin "91") (pinfunction "(ADC6/TDO)PF6_91") (pintype "bidirectional"))
    )
    (net (code "160") (name "unconnected-(U5-(ADC7{slash}TDI)PF7-Pad90)") (class "Default")
      (node (ref "U5") (pin "90") (pinfunction "(ADC7/TDI)PF7_90") (pintype "bidirectional"))
    )
    (net (code "161") (name "unconnected-(U5-(CLKO{slash}ICP3{slash}INT7)PE7-Pad9)") (class "Default")
      (node (ref "U5") (pin "9") (pinfunction "(CLKO/ICP3/INT7)PE7_9") (pintype "bidirectional"))
    )
    (net (code "162") (name "unconnected-(U5-(ICP1)PD4-Pad47)") (class "Default")
      (node (ref "U5") (pin "47") (pinfunction "(ICP1)PD4_47") (pintype "bidirectional"))
    )
    (net (code "163") (name "unconnected-(U5-(OC0A{slash}OC1C{slash}PCINT7)PB7-Pad26)") (class "Default")
      (node (ref "U5") (pin "26") (pinfunction "(OC0A/OC1C/PCINT7)PB7_26") (pintype "bidirectional"))
    )
    (net (code "164") (name "unconnected-(U5-(OC0B)PG5-Pad1)") (class "Default")
      (node (ref "U5") (pin "1") (pinfunction "(OC0B)PG5_1") (pintype "bidirectional"))
    )
    (net (code "165") (name "unconnected-(U5-(SS{slash}PCINT0)PB0-Pad19)") (class "Default")
      (node (ref "U5") (pin "19") (pinfunction "(SS/PCINT0)PB0_19") (pintype "bidirectional"))
    )
    (net (code "166") (name "unconnected-(U5-(T0)PD7-Pad50)") (class "Default")
      (node (ref "U5") (pin "50") (pinfunction "(T0)PD7_50") (pintype "bidirectional"))
    )
    (net (code "167") (name "unconnected-(U5-(T1)PD6-Pad49)") (class "Default")
      (node (ref "U5") (pin "49") (pinfunction "(T1)PD6_49") (pintype "bidirectional"))
    )
    (net (code "168") (name "unconnected-(U5-(T3{slash}INT6)PE6-Pad8)") (class "Default")
      (node (ref "U5") (pin "8") (pinfunction "(T3/INT6)PE6_8") (pintype "bidirectional"))
    )
    (net (code "169") (name "unconnected-(U5-(TOSC1)PG4-Pad29)") (class "Default")
      (node (ref "U5") (pin "29") (pinfunction "(TOSC1)PG4_29") (pintype "bidirectional"))
    )
    (net (code "170") (name "unconnected-(U5-(TOSC2)PG3-Pad28)") (class "Default")
      (node (ref "U5") (pin "28") (pinfunction "(TOSC2)PG3_28") (pintype "bidirectional"))
    )
    (net (code "171") (name "unconnected-(U5-(XCK0{slash}AIN0)PE2-Pad4)") (class "Default")
      (node (ref "U5") (pin "4") (pinfunction "(XCK0/AIN0)PE2_4") (pintype "bidirectional"))
    )
    (net (code "172") (name "unconnected-(U5-(XCK1)PD5-Pad48)") (class "Default")
      (node (ref "U5") (pin "48") (pinfunction "(XCK1)PD5_48") (pintype "bidirectional"))
    )
    (net (code "173") (name "unconnected-(U5-PH2(XCK2)-Pad14)") (class "Default")
      (node (ref "U5") (pin "14") (pinfunction "PH2(XCK2)_14") (pintype "bidirectional"))
    )
    (net (code "174") (name "unconnected-(U5-PH7(T4)-Pad27)") (class "Default")
      (node (ref "U5") (pin "27") (pinfunction "PH7(T4)_27") (pintype "bidirectional"))
    )
    (net (code "175") (name "unconnected-(U5-PJ2(XCK3{slash}PCINT11)-Pad65)") (class "Default")
      (node (ref "U5") (pin "65") (pinfunction "PJ2(XCK3/PCINT11)_65") (pintype "bidirectional"))
    )
    (net (code "176") (name "unconnected-(U5-PJ3(PCINT12)-Pad66)") (class "Default")
      (node (ref "U5") (pin "66") (pinfunction "PJ3(PCINT12)_66") (pintype "bidirectional"))
    )
    (net (code "177") (name "unconnected-(U5-PJ4(PCINT13)-Pad67)") (class "Default")
      (node (ref "U5") (pin "67") (pinfunction "PJ4(PCINT13)_67") (pintype "bidirectional"))
    )
    (net (code "178") (name "unconnected-(U5-PJ5(PCINT14)-Pad68)") (class "Default")
      (node (ref "U5") (pin "68") (pinfunction "PJ5(PCINT14)_68") (pintype "bidirectional"))
    )
    (net (code "179") (name "unconnected-(U5-PJ6(PCINT15)-Pad69)") (class "Default")
      (node (ref "U5") (pin "69") (pinfunction "PJ6(PCINT15)_69") (pintype "bidirectional"))
    )
    (net (code "180") (name "unconnected-(U5-PJ7-Pad79)") (class "Default")
      (node (ref "U5") (pin "79") (pinfunction "PJ7_79") (pintype "bidirectional"))
    )
    (net (code "181") (name "unconnected-(U5-PK0(ADC8{slash}PCINT16)-Pad89)") (class "Default")
      (node (ref "U5") (pin "89") (pinfunction "PK0(ADC8/PCINT16)_89") (pintype "bidirectional"))
    )
    (net (code "182") (name "unconnected-(U5-PK4(ADC12{slash}PCINT20)-Pad85)") (class "Default")
      (node (ref "U5") (pin "85") (pinfunction "PK4(ADC12/PCINT20)_85") (pintype "bidirectional"))
    )
    (net (code "183") (name "unconnected-(U5-PK5(ADC13{slash}PCINT21)-Pad84)") (class "Default")
      (node (ref "U5") (pin "84") (pinfunction "PK5(ADC13/PCINT21)_84") (pintype "bidirectional"))
    )
    (net (code "184") (name "unconnected-(U5-PK6(ADC14{slash}PCINT22)-Pad83)") (class "Default")
      (node (ref "U5") (pin "83") (pinfunction "PK6(ADC14/PCINT22)_83") (pintype "bidirectional"))
    )
    (net (code "185") (name "unconnected-(U5-PK7(ADC15{slash}PCINT23)-Pad82)") (class "Default")
      (node (ref "U5") (pin "82") (pinfunction "PK7(ADC15/PCINT23)_82") (pintype "bidirectional"))
    )
    (net (code "186") (name "unconnected-(U5-PL2(T5)-Pad37)") (class "Default")
      (node (ref "U5") (pin "37") (pinfunction "PL2(T5)_37") (pintype "bidirectional"))
    )
    (net (code "187") (name "unconnected-(U5-PL3(OC5A)-Pad38)") (class "Default")
      (node (ref "U5") (pin "38") (pinfunction "PL3(OC5A)_38") (pintype "bidirectional"))
    )
    (net (code "188") (name "unconnected-(U5-PL5(OC5C)-Pad40)") (class "Default")
      (node (ref "U5") (pin "40") (pinfunction "PL5(OC5C)_40") (pintype "bidirectional"))
    )
  )
)
